# INPUT_STAGE.net
KiCad netlist of a schematic drawn in Altium Designer
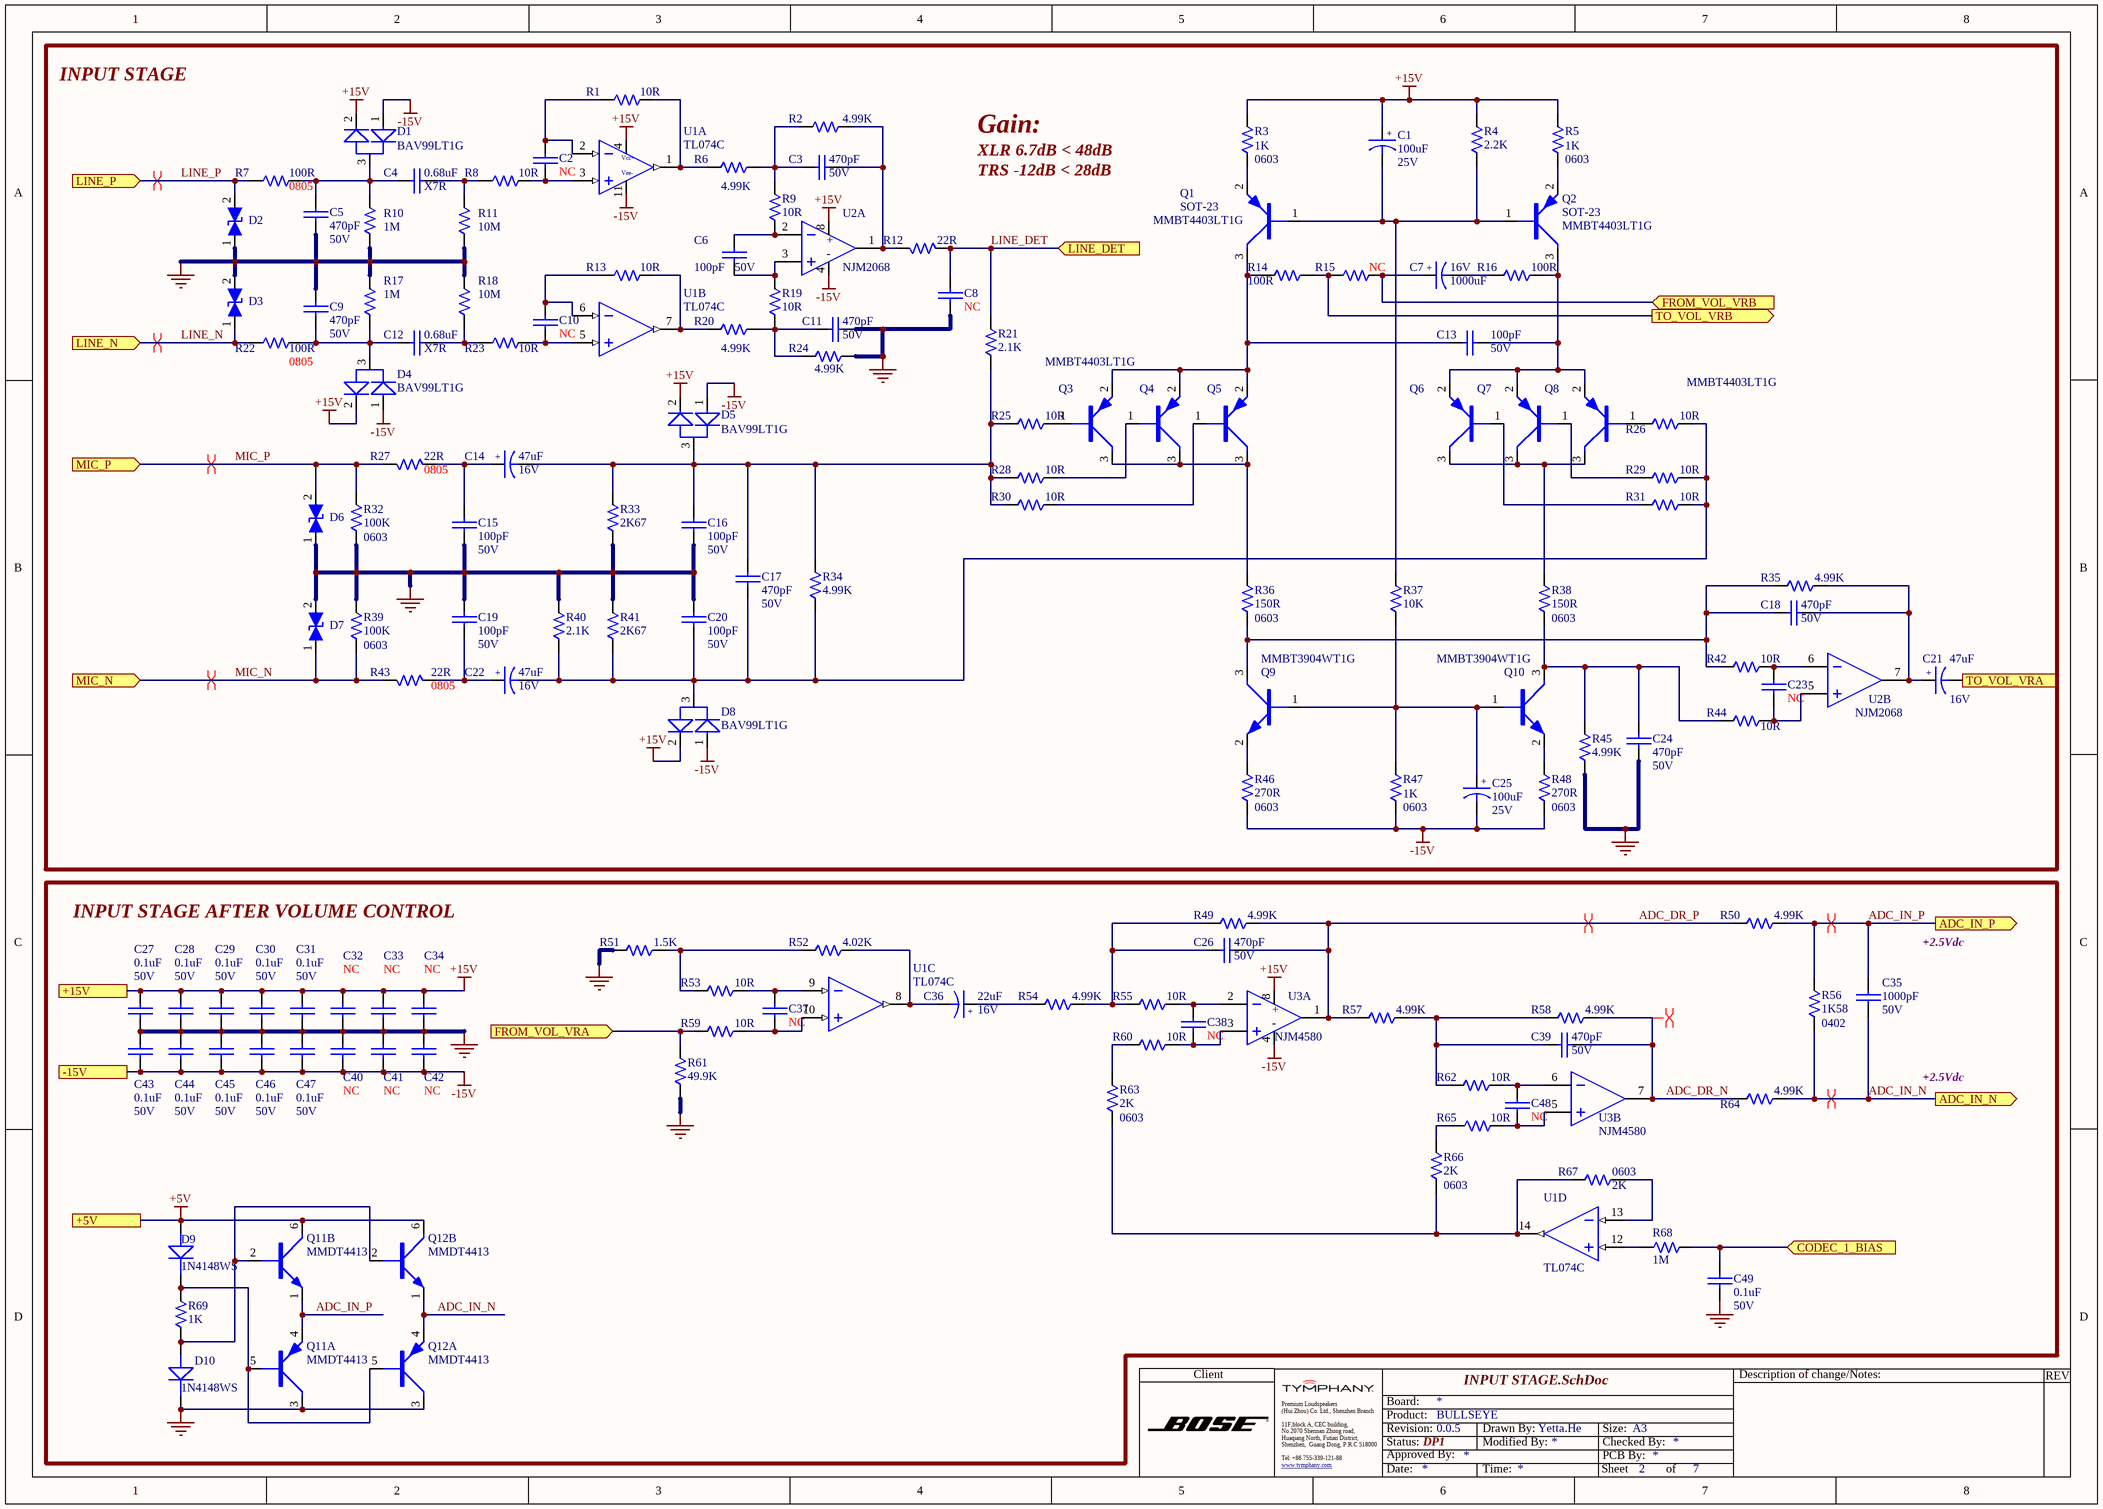
[diagram p0: INPUT STAGE.SchDoc]

(export (version "E")
  (design (tool "Eeschema 10.0.6"))
  (components
    (comp (ref "C1")
      (value "100uF")
      (footprint "CASE - D8")
      (description "E 100UF 25V +-20% 6.3X7. VEJ101M1E K")
      (fields
        (field (name "MFG") "LELON")
        (field (name "MFG PART") "VEJ101M1ETR-0607")
        (field (name "VOLTAGE") "25V")
        (field (name "CREATE_NAME") "Nathan")
      )
      (libsource (lib "P-Capacitors") (part "CAP E 100uF 25V 20% SMD_VEJ101M1ETR-0607"))
    )
    (comp (ref "C2")
      (value "NC")
      (footprint "CAPC0603-RW")
      (fields (field (name "Comment") "CAP0603 NC") (field (name "CREATE_NAME") "Tom"))
      (libsource (lib "Temporary") (part "CAP0603 NC"))
    )
    (comp (ref "C3")
      (value "470pF")
      (footprint "CAPC0603-RW")
      (description "CAP NPO 470PF 50V +-2% 0603 WALSIN L")
      (fields
        (field (name "MFG") "WALSIN")
        (field (name "TOLERANCE") "2%")
        (field (name "VOLTAGE") "50V")
        (field (name "CREATE_NAME") "Nathan")
      )
      (libsource (lib "P-Capacitors") (part "CAP0603 470pF 50V 2%_NPO_WALSIN"))
    )
    (comp (ref "C4")
      (value "0.68uF")
      (footprint "CAPC1206-RW")
      (description "CHIP CAP 0.68uF 25V 10% 1206 X7R")
      (fields
        (field (name "OTHER") "X7R")
        (field (name "TOLERANCE") "10%")
        (field (name "Comment") "PZL456450-6840")
      )
      (libsource (lib "P-Capacitors") (part "CAP1206 0.68uF 25V 10%"))
    )
    (comp (ref "C5")
      (value "470pF")
      (footprint "CAPC0603-RW")
      (description "CAP NPO 470PF 50V +-2% 0603 WALSIN L")
      (fields
        (field (name "MFG") "WALSIN")
        (field (name "TOLERANCE") "2%")
        (field (name "VOLTAGE") "50V")
        (field (name "CREATE_NAME") "Nathan")
      )
      (libsource (lib "P-Capacitors") (part "CAP0603 470pF 50V 2%_NPO_WALSIN"))
    )
    (comp (ref "C6")
      (value "100pF")
      (footprint "CAPC0603-RW")
      (description "CAP NPO 100PF 50V +-2% 0603 WALSIN L")
      (fields
        (field (name "MFG") "WALSIN")
        (field (name "TOLERANCE") "2%")
        (field (name "VOLTAGE") "50V")
        (field (name "CREATE_NAME") "Nathan")
      )
      (libsource (lib "P-Capacitors") (part "CAP0603 100pF 50V 2%_NPO_WALSIN"))
    )
    (comp (ref "C7")
      (value "1000uF")
      (footprint "CAP_Radial_D8L16P3.5")
      (description "E 1000U 16V +-20% 8X15MM RXW102M1C K")
      (fields
        (field (name "MFG") "LELON")
        (field (name "MFG PART") "RXW102M1CBKF0815")
        (field (name "VOLTAGE") "16V")
        (field (name "CREATE_NAME") "Nathan")
      )
      (libsource (lib "P-Capacitors") (part "CAP E Aluminum 1000uF 16V 20%_RXW102M1CBKF0815"))
    )
    (comp (ref "C8")
      (value "NC")
      (footprint "CAPC0603-RW")
      (fields (field (name "Comment") "CAP0603 NC") (field (name "CREATE_NAME") "Tom"))
      (libsource (lib "Temporary") (part "CAP0603 NC"))
    )
    (comp (ref "C9")
      (value "470pF")
      (footprint "CAPC0603-RW")
      (description "CAP NPO 470PF 50V +-2% 0603 WALSIN L")
      (fields
        (field (name "MFG") "WALSIN")
        (field (name "TOLERANCE") "2%")
        (field (name "VOLTAGE") "50V")
        (field (name "CREATE_NAME") "Nathan")
      )
      (libsource (lib "P-Capacitors") (part "CAP0603 470pF 50V 2%_NPO_WALSIN"))
    )
    (comp (ref "C10")
      (value "NC")
      (footprint "CAPC0603-RW")
      (fields (field (name "Comment") "CAP0603 NC") (field (name "CREATE_NAME") "Tom"))
      (libsource (lib "Temporary") (part "CAP0603 NC"))
    )
    (comp (ref "C11")
      (value "470pF")
      (footprint "CAPC0603-RW")
      (description "CAP NPO 470PF 50V +-2% 0603 WALSIN L")
      (fields
        (field (name "MFG") "WALSIN")
        (field (name "TOLERANCE") "2%")
        (field (name "VOLTAGE") "50V")
        (field (name "CREATE_NAME") "Nathan")
      )
      (libsource (lib "P-Capacitors") (part "CAP0603 470pF 50V 2%_NPO_WALSIN"))
    )
    (comp (ref "C12")
      (value "0.68uF")
      (footprint "CAPC1206-RW")
      (description "CHIP CAP 0.68uF 25V 10% 1206 X7R")
      (fields
        (field (name "OTHER") "X7R")
        (field (name "TOLERANCE") "10%")
        (field (name "Comment") "PZL456450-6840")
      )
      (libsource (lib "P-Capacitors") (part "CAP1206 0.68uF 25V 10%"))
    )
    (comp (ref "C13")
      (value "100pF")
      (footprint "CAPC0603-RW")
      (description "CAP NPO 100PF 50V +-2% 0603 WALSIN L")
      (fields
        (field (name "MFG") "WALSIN")
        (field (name "TOLERANCE") "2%")
        (field (name "VOLTAGE") "50V")
        (field (name "CREATE_NAME") "Nathan")
      )
      (libsource (lib "P-Capacitors") (part "CAP0603 100pF 50V 2%_NPO_WALSIN"))
    )
    (comp (ref "C14")
      (value "47uF")
      (footprint "CASE - C5.7")
      (description "E 47UF 16V +-20% 5X6 VEJ470M1C K")
      (fields
        (field (name "MFG") "LELON")
        (field (name "MFG PART") "VEJ470M1CTR-0506")
        (field (name "VOLTAGE") "16V")
        (field (name "CREATE_NAME") "Nathan")
      )
      (libsource (lib "P-Capacitors") (part "CAP E 47uF 16V 20% SMD_VEJ470M1CTR-0506"))
    )
    (comp (ref "C15")
      (value "100pF")
      (footprint "CAPC0603-RW")
      (description "CAP NPO 100PF 50V +-2% 0603 WALSIN L")
      (fields
        (field (name "MFG") "WALSIN")
        (field (name "TOLERANCE") "2%")
        (field (name "VOLTAGE") "50V")
        (field (name "CREATE_NAME") "Nathan")
      )
      (libsource (lib "P-Capacitors") (part "CAP0603 100pF 50V 2%_NPO_WALSIN"))
    )
    (comp (ref "C16")
      (value "100pF")
      (footprint "CAPC0603-RW")
      (description "CAP NPO 100PF 50V +-2% 0603 WALSIN L")
      (fields
        (field (name "MFG") "WALSIN")
        (field (name "TOLERANCE") "2%")
        (field (name "VOLTAGE") "50V")
        (field (name "CREATE_NAME") "Nathan")
      )
      (libsource (lib "P-Capacitors") (part "CAP0603 100pF 50V 2%_NPO_WALSIN"))
    )
    (comp (ref "C17")
      (value "470pF")
      (footprint "CAPC0603-RW")
      (description "CAP NPO 470PF 50V +-2% 0603 WALSIN L")
      (fields
        (field (name "MFG") "WALSIN")
        (field (name "TOLERANCE") "2%")
        (field (name "VOLTAGE") "50V")
        (field (name "CREATE_NAME") "Nathan")
      )
      (libsource (lib "P-Capacitors") (part "CAP0603 470pF 50V 2%_NPO_WALSIN"))
    )
    (comp (ref "C18")
      (value "470pF")
      (footprint "CAPC0603-RW")
      (description "CAP NPO 470PF 50V +-2% 0603 WALSIN L")
      (fields
        (field (name "MFG") "WALSIN")
        (field (name "TOLERANCE") "2%")
        (field (name "VOLTAGE") "50V")
        (field (name "CREATE_NAME") "Nathan")
      )
      (libsource (lib "P-Capacitors") (part "CAP0603 470pF 50V 2%_NPO_WALSIN"))
    )
    (comp (ref "C19")
      (value "100pF")
      (footprint "CAPC0603-RW")
      (description "CAP NPO 100PF 50V +-2% 0603 WALSIN L")
      (fields
        (field (name "MFG") "WALSIN")
        (field (name "TOLERANCE") "2%")
        (field (name "VOLTAGE") "50V")
        (field (name "CREATE_NAME") "Nathan")
      )
      (libsource (lib "P-Capacitors") (part "CAP0603 100pF 50V 2%_NPO_WALSIN"))
    )
    (comp (ref "C20")
      (value "100pF")
      (footprint "CAPC0603-RW")
      (description "CAP NPO 100PF 50V +-2% 0603 WALSIN L")
      (fields
        (field (name "MFG") "WALSIN")
        (field (name "TOLERANCE") "2%")
        (field (name "VOLTAGE") "50V")
        (field (name "CREATE_NAME") "Nathan")
      )
      (libsource (lib "P-Capacitors") (part "CAP0603 100pF 50V 2%_NPO_WALSIN"))
    )
    (comp (ref "C21")
      (value "47uF")
      (footprint "CASE - C5.7")
      (description "E 47UF 16V +-20% 5X6 VEJ470M1C K")
      (fields
        (field (name "MFG") "LELON")
        (field (name "MFG PART") "VEJ470M1CTR-0506")
        (field (name "VOLTAGE") "16V")
        (field (name "CREATE_NAME") "Nathan")
      )
      (libsource (lib "P-Capacitors") (part "CAP E 47uF 16V 20% SMD_VEJ470M1CTR-0506"))
    )
    (comp (ref "C22")
      (value "47uF")
      (footprint "CASE - C5.7")
      (description "E 47UF 16V +-20% 5X6 VEJ470M1C K")
      (fields
        (field (name "MFG") "LELON")
        (field (name "MFG PART") "VEJ470M1CTR-0506")
        (field (name "VOLTAGE") "16V")
        (field (name "CREATE_NAME") "Nathan")
      )
      (libsource (lib "P-Capacitors") (part "CAP E 47uF 16V 20% SMD_VEJ470M1CTR-0506"))
    )
    (comp (ref "C23")
      (value "NC")
      (footprint "CAPC0603-RW")
      (fields (field (name "Comment") "CAP0603 NC") (field (name "CREATE_NAME") "Tom"))
      (libsource (lib "Temporary") (part "CAP0603 NC"))
    )
    (comp (ref "C24")
      (value "470pF")
      (footprint "CAPC0603-RW")
      (description "CAP NPO 470PF 50V +-2% 0603 WALSIN L")
      (fields
        (field (name "MFG") "WALSIN")
        (field (name "TOLERANCE") "2%")
        (field (name "VOLTAGE") "50V")
        (field (name "CREATE_NAME") "Nathan")
      )
      (libsource (lib "P-Capacitors") (part "CAP0603 470pF 50V 2%_NPO_WALSIN"))
    )
    (comp (ref "C25")
      (value "100uF")
      (footprint "CASE - D8")
      (description "E 100UF 25V +-20% 6.3X7. VEJ101M1E K")
      (fields
        (field (name "MFG") "LELON")
        (field (name "MFG PART") "VEJ101M1ETR-0607")
        (field (name "VOLTAGE") "25V")
        (field (name "CREATE_NAME") "Nathan")
      )
      (libsource (lib "P-Capacitors") (part "CAP E 100uF 25V 20% SMD_VEJ101M1ETR-0607"))
    )
    (comp (ref "C26")
      (value "470pF")
      (footprint "CAPC0603-RW")
      (description "CAP NPO 470PF 50V +-2% 0603 WALSIN L")
      (fields
        (field (name "MFG") "WALSIN")
        (field (name "TOLERANCE") "2%")
        (field (name "VOLTAGE") "50V")
        (field (name "CREATE_NAME") "Nathan")
      )
      (libsource (lib "P-Capacitors") (part "CAP0603 470pF 50V 2%_NPO_WALSIN"))
    )
    (comp (ref "C27")
      (value "0.1uF")
      (footprint "CAPC0402-RW")
      (description "CAP, CER, 0.1uF, 10%, 50V, X7R, 0402, RoHS")
      (fields
        (field (name "TOLERANCE") "10%")
        (field (name "VOLTAGE") "50V")
        (field (name "Comment") "PWL456470-1040")
        (field (name "CREATE_NAME") "TOM@Deftronics")
      )
      (libsource (lib "P-Capacitors") (part "CAP0402 0.1uF 50V 10%"))
    )
    (comp (ref "C28")
      (value "0.1uF")
      (footprint "CAPC0402-RW")
      (description "CAP, CER, 0.1uF, 10%, 50V, X7R, 0402, RoHS")
      (fields
        (field (name "TOLERANCE") "10%")
        (field (name "VOLTAGE") "50V")
        (field (name "Comment") "PWL456470-1040")
        (field (name "CREATE_NAME") "TOM@Deftronics")
      )
      (libsource (lib "P-Capacitors") (part "CAP0402 0.1uF 50V 10%"))
    )
    (comp (ref "C29")
      (value "0.1uF")
      (footprint "CAPC0402-RW")
      (description "CAP, CER, 0.1uF, 10%, 50V, X7R, 0402, RoHS")
      (fields
        (field (name "TOLERANCE") "10%")
        (field (name "VOLTAGE") "50V")
        (field (name "Comment") "PWL456470-1040")
        (field (name "CREATE_NAME") "TOM@Deftronics")
      )
      (libsource (lib "P-Capacitors") (part "CAP0402 0.1uF 50V 10%"))
    )
    (comp (ref "C30")
      (value "0.1uF")
      (footprint "CAPC0402-RW")
      (description "CAP, CER, 0.1uF, 10%, 50V, X7R, 0402, RoHS")
      (fields
        (field (name "TOLERANCE") "10%")
        (field (name "VOLTAGE") "50V")
        (field (name "Comment") "PWL456470-1040")
        (field (name "CREATE_NAME") "TOM@Deftronics")
      )
      (libsource (lib "P-Capacitors") (part "CAP0402 0.1uF 50V 10%"))
    )
    (comp (ref "C31")
      (value "0.1uF")
      (footprint "CAPC0402-RW")
      (description "CAP, CER, 0.1uF, 10%, 50V, X7R, 0402, RoHS")
      (fields
        (field (name "TOLERANCE") "10%")
        (field (name "VOLTAGE") "50V")
        (field (name "Comment") "PWL456470-1040")
        (field (name "CREATE_NAME") "TOM@Deftronics")
      )
      (libsource (lib "P-Capacitors") (part "CAP0402 0.1uF 50V 10%"))
    )
    (comp (ref "C32")
      (value "NC")
      (footprint "CAPC0603-RW")
      (fields (field (name "Comment") "CAP0603 NC") (field (name "CREATE_NAME") "Tom"))
      (libsource (lib "Temporary") (part "CAP0603 NC"))
    )
    (comp (ref "C33")
      (value "NC")
      (footprint "CAPC0603-RW")
      (fields (field (name "Comment") "CAP0603 NC") (field (name "CREATE_NAME") "Tom"))
      (libsource (lib "Temporary") (part "CAP0603 NC"))
    )
    (comp (ref "C34")
      (value "NC")
      (footprint "CAPC0603-RW")
      (fields (field (name "Comment") "CAP0603 NC") (field (name "CREATE_NAME") "Tom"))
      (libsource (lib "Temporary") (part "CAP0603 NC"))
    )
    (comp (ref "C35")
      (value "1000pF")
      (footprint "CAPC0603-RW")
      (description "CAP NPO 1000P 50V +-2% 0603 WALSIN L")
      (fields
        (field (name "MFG") "WALSIN")
        (field (name "TOLERANCE") "2%")
        (field (name "VOLTAGE") "50V")
        (field (name "CREATE_NAME") "Nathan")
      )
      (libsource (lib "P-Capacitors") (part "CAP0603 1000pF 50V 2%_NPO_WALSIN"))
    )
    (comp (ref "C36")
      (value "22uF")
      (footprint "CASE - B")
      (description "E 22UF 16V +-20% 4.3X4. VEJ220M1C K")
      (fields
        (field (name "MFG") "LELON")
        (field (name "MFG PART") "VEJ220M1CTR-0405")
        (field (name "VOLTAGE") "16V")
        (field (name "CREATE_NAME") "Nathan")
      )
      (libsource (lib "P-Capacitors") (part "CAP E 22uF 16V 20% SMD_VEJ220M1CTR-0405"))
    )
    (comp (ref "C37")
      (value "NC")
      (footprint "CAPC0603-RW")
      (fields (field (name "Comment") "CAP0603 NC") (field (name "CREATE_NAME") "Tom"))
      (libsource (lib "Temporary") (part "CAP0603 NC"))
    )
    (comp (ref "C38")
      (value "NC")
      (footprint "CAPC0603-RW")
      (fields (field (name "Comment") "CAP0603 NC") (field (name "CREATE_NAME") "Tom"))
      (libsource (lib "Temporary") (part "CAP0603 NC"))
    )
    (comp (ref "C39")
      (value "470pF")
      (footprint "CAPC0603-RW")
      (description "CAP NPO 470PF 50V +-2% 0603 WALSIN L")
      (fields
        (field (name "MFG") "WALSIN")
        (field (name "TOLERANCE") "2%")
        (field (name "VOLTAGE") "50V")
        (field (name "CREATE_NAME") "Nathan")
      )
      (libsource (lib "P-Capacitors") (part "CAP0603 470pF 50V 2%_NPO_WALSIN"))
    )
    (comp (ref "C40")
      (value "NC")
      (footprint "CAPC0603-RW")
      (fields (field (name "Comment") "CAP0603 NC") (field (name "CREATE_NAME") "Tom"))
      (libsource (lib "Temporary") (part "CAP0603 NC"))
    )
    (comp (ref "C41")
      (value "NC")
      (footprint "CAPC0603-RW")
      (fields (field (name "Comment") "CAP0603 NC") (field (name "CREATE_NAME") "Tom"))
      (libsource (lib "Temporary") (part "CAP0603 NC"))
    )
    (comp (ref "C42")
      (value "NC")
      (footprint "CAPC0603-RW")
      (fields (field (name "Comment") "CAP0603 NC") (field (name "CREATE_NAME") "Tom"))
      (libsource (lib "Temporary") (part "CAP0603 NC"))
    )
    (comp (ref "C43")
      (value "0.1uF")
      (footprint "CAPC0402-RW")
      (description "CAP, CER, 0.1uF, 10%, 50V, X7R, 0402, RoHS")
      (fields
        (field (name "TOLERANCE") "10%")
        (field (name "VOLTAGE") "50V")
        (field (name "Comment") "PWL456470-1040")
        (field (name "CREATE_NAME") "TOM@Deftronics")
      )
      (libsource (lib "P-Capacitors") (part "CAP0402 0.1uF 50V 10%"))
    )
    (comp (ref "C44")
      (value "0.1uF")
      (footprint "CAPC0402-RW")
      (description "CAP, CER, 0.1uF, 10%, 50V, X7R, 0402, RoHS")
      (fields
        (field (name "TOLERANCE") "10%")
        (field (name "VOLTAGE") "50V")
        (field (name "Comment") "PWL456470-1040")
        (field (name "CREATE_NAME") "TOM@Deftronics")
      )
      (libsource (lib "P-Capacitors") (part "CAP0402 0.1uF 50V 10%"))
    )
    (comp (ref "C45")
      (value "0.1uF")
      (footprint "CAPC0402-RW")
      (description "CAP, CER, 0.1uF, 10%, 50V, X7R, 0402, RoHS")
      (fields
        (field (name "TOLERANCE") "10%")
        (field (name "VOLTAGE") "50V")
        (field (name "Comment") "PWL456470-1040")
        (field (name "CREATE_NAME") "TOM@Deftronics")
      )
      (libsource (lib "P-Capacitors") (part "CAP0402 0.1uF 50V 10%"))
    )
    (comp (ref "C46")
      (value "0.1uF")
      (footprint "CAPC0402-RW")
      (description "CAP, CER, 0.1uF, 10%, 50V, X7R, 0402, RoHS")
      (fields
        (field (name "TOLERANCE") "10%")
        (field (name "VOLTAGE") "50V")
        (field (name "Comment") "PWL456470-1040")
        (field (name "CREATE_NAME") "TOM@Deftronics")
      )
      (libsource (lib "P-Capacitors") (part "CAP0402 0.1uF 50V 10%"))
    )
    (comp (ref "C47")
      (value "0.1uF")
      (footprint "CAPC0402-RW")
      (description "CAP, CER, 0.1uF, 10%, 50V, X7R, 0402, RoHS")
      (fields
        (field (name "TOLERANCE") "10%")
        (field (name "VOLTAGE") "50V")
        (field (name "Comment") "PWL456470-1040")
        (field (name "CREATE_NAME") "TOM@Deftronics")
      )
      (libsource (lib "P-Capacitors") (part "CAP0402 0.1uF 50V 10%"))
    )
    (comp (ref "C48")
      (value "NC")
      (footprint "CAPC0603-RW")
      (fields (field (name "Comment") "CAP0603 NC") (field (name "CREATE_NAME") "Tom"))
      (libsource (lib "Temporary") (part "CAP0603 NC"))
    )
    (comp (ref "C49")
      (value "0.1uF")
      (footprint "CAPC0402-RW")
      (description "CAP, CER, 0.1uF, 10%, 50V, X7R, 0402, RoHS")
      (fields
        (field (name "TOLERANCE") "10%")
        (field (name "VOLTAGE") "50V")
        (field (name "Comment") "PWL456470-1040")
        (field (name "CREATE_NAME") "TOM@Deftronics")
      )
      (libsource (lib "P-Capacitors") (part "CAP0402 0.1uF 50V 10%"))
    )
    (comp (ref "D1")
      (value "RCD100099-0010")
      (footprint "SOT23-132-RW")
      (description "SWITC 70V 215MA BAV99LT1G ON SE G")
      (fields
        (field (name "MFG") "ON SEMI")
        (field (name "VOLTAGE") "100V")
        (field (name "MFG PART") "BAV99LT1G")
      )
      (libsource (lib "R-Semiconductors") (part "BAV99LT1G"))
    )
    (comp (ref "D2")
      (value "T710500020400")
      (footprint "VAR-0402")
      (description "VR AVRM1005C120MTAAB TDK K")
      (fields
        (field (name "MFG") "TDK")
        (field (name "MFG PART") "AVRM1005C120MTAAB")
        (field (name "CREAT NAME") "QCD")
      )
      (libsource (lib "R-Semiconductors") (part "AVRM1005C120MTAAB"))
    )
    (comp (ref "D3")
      (value "T710500020400")
      (footprint "VAR-0402")
      (description "VR AVRM1005C120MTAAB TDK K")
      (fields
        (field (name "MFG") "TDK")
        (field (name "MFG PART") "AVRM1005C120MTAAB")
        (field (name "CREAT NAME") "QCD")
      )
      (libsource (lib "R-Semiconductors") (part "AVRM1005C120MTAAB"))
    )
    (comp (ref "D4")
      (value "RCD100099-0010")
      (footprint "SOT23-132-RW")
      (description "SWITC 70V 215MA BAV99LT1G ON SE G")
      (fields
        (field (name "MFG") "ON SEMI")
        (field (name "VOLTAGE") "100V")
        (field (name "MFG PART") "BAV99LT1G")
      )
      (libsource (lib "R-Semiconductors") (part "BAV99LT1G"))
    )
    (comp (ref "D5")
      (value "RCD100099-0010")
      (footprint "SOT23-132-RW")
      (description "SWITC 70V 215MA BAV99LT1G ON SE G")
      (fields
        (field (name "MFG") "ON SEMI")
        (field (name "VOLTAGE") "100V")
        (field (name "MFG PART") "BAV99LT1G")
      )
      (libsource (lib "R-Semiconductors") (part "BAV99LT1G"))
    )
    (comp (ref "D6")
      (value "T710500020400")
      (footprint "VAR-0402")
      (description "VR AVRM1005C120MTAAB TDK K")
      (fields
        (field (name "MFG") "TDK")
        (field (name "MFG PART") "AVRM1005C120MTAAB")
        (field (name "CREAT NAME") "QCD")
      )
      (libsource (lib "R-Semiconductors") (part "AVRM1005C120MTAAB"))
    )
    (comp (ref "D7")
      (value "T710500020400")
      (footprint "VAR-0402")
      (description "VR AVRM1005C120MTAAB TDK K")
      (fields
        (field (name "MFG") "TDK")
        (field (name "MFG PART") "AVRM1005C120MTAAB")
        (field (name "CREAT NAME") "QCD")
      )
      (libsource (lib "R-Semiconductors") (part "AVRM1005C120MTAAB"))
    )
    (comp (ref "D8")
      (value "RCD100099-0010")
      (footprint "SOT23-132-RW")
      (description "SWITC 70V 215MA BAV99LT1G ON SE G")
      (fields
        (field (name "MFG") "ON SEMI")
        (field (name "VOLTAGE") "100V")
        (field (name "MFG PART") "BAV99LT1G")
      )
      (libsource (lib "R-Semiconductors") (part "BAV99LT1G"))
    )
    (comp (ref "D9")
      (value "RCD114148-0020")
      (footprint "SOD-323")
      (description "DIODE SW 1N4148 VF=0.7V SOD-323")
      (fields
        (field (name "MFG") "TW SEMICONDUCTOR")
        (field (name "VOLTAGE") "100V")
        (field (name "MFG PART") "1N4148WS")
      )
      (libsource (lib "R-Semiconductors") (part "1N4148WS"))
    )
    (comp (ref "D10")
      (value "RCD114148-0020")
      (footprint "SOD-323")
      (description "DIODE SW 1N4148 VF=0.7V SOD-323")
      (fields
        (field (name "MFG") "TW SEMICONDUCTOR")
        (field (name "VOLTAGE") "100V")
        (field (name "MFG PART") "1N4148WS")
      )
      (libsource (lib "R-Semiconductors") (part "1N4148WS"))
    )
    (comp (ref "Q1")
      (value "T582003100440")
      (footprint "SOT23-132-RW")
      (description "PNP -40V MMBT4403LT1G SOT23 ON K")
      (fields
        (field (name "MFG") "ON")
        (field (name "VOLTAGE") "40V")
        (field (name "PACKAGE") "SOT-23")
        (field (name "MFG PART") "MMBT4403LT1G")
        (field (name "CREATE NAME") "Nathan")
      )
      (libsource (lib "R-Semiconductors") (part "MMBT4403LT1G"))
    )
    (comp (ref "Q2")
      (value "T582003100440")
      (footprint "SOT23-132-RW")
      (description "PNP -40V MMBT4403LT1G SOT23 ON K")
      (fields
        (field (name "MFG") "ON")
        (field (name "VOLTAGE") "40V")
        (field (name "PACKAGE") "SOT-23")
        (field (name "MFG PART") "MMBT4403LT1G")
        (field (name "CREATE NAME") "Nathan")
      )
      (libsource (lib "R-Semiconductors") (part "MMBT4403LT1G"))
    )
    (comp (ref "Q3")
      (value "T582003100440")
      (footprint "SOT23-132-RW")
      (description "PNP -40V MMBT4403LT1G SOT23 ON K")
      (fields
        (field (name "MFG") "ON")
        (field (name "VOLTAGE") "40V")
        (field (name "MFG PART") "MMBT4403LT1G")
        (field (name "CREATE NAME") "Nathan")
      )
      (libsource (lib "R-Semiconductors") (part "MMBT4403LT1G"))
    )
    (comp (ref "Q4")
      (value "T582003100440")
      (footprint "SOT23-132-RW")
      (description "PNP -40V MMBT4403LT1G SOT23 ON K")
      (fields (field (name "MFG") "ON") (field (name "VOLTAGE") "40V") (field (name "CREATE NAME") "Nathan"))
      (libsource (lib "R-Semiconductors") (part "MMBT4403LT1G"))
    )
    (comp (ref "Q5")
      (value "T582003100440")
      (footprint "SOT23-132-RW")
      (description "PNP -40V MMBT4403LT1G SOT23 ON K")
      (fields (field (name "MFG") "ON") (field (name "VOLTAGE") "40V") (field (name "CREATE NAME") "Nathan"))
      (libsource (lib "R-Semiconductors") (part "MMBT4403LT1G"))
    )
    (comp (ref "Q6")
      (value "T582003100440")
      (footprint "SOT23-132-RW")
      (description "PNP -40V MMBT4403LT1G SOT23 ON K")
      (fields (field (name "MFG") "ON") (field (name "VOLTAGE") "40V") (field (name "CREATE NAME") "Nathan"))
      (libsource (lib "R-Semiconductors") (part "MMBT4403LT1G"))
    )
    (comp (ref "Q7")
      (value "T582003100440")
      (footprint "SOT23-132-RW")
      (description "PNP -40V MMBT4403LT1G SOT23 ON K")
      (fields (field (name "MFG") "ON") (field (name "VOLTAGE") "40V") (field (name "CREATE NAME") "Nathan"))
      (libsource (lib "R-Semiconductors") (part "MMBT4403LT1G"))
    )
    (comp (ref "Q8")
      (value "T582003100440")
      (footprint "SOT23-132-RW")
      (description "PNP -40V MMBT4403LT1G SOT23 ON K")
      (fields
        (field (name "MFG") "ON")
        (field (name "VOLTAGE") "40V")
        (field (name "MFG PART") "MMBT4403LT1G")
        (field (name "CREATE NAME") "Nathan")
      )
      (libsource (lib "R-Semiconductors") (part "MMBT4403LT1G"))
    )
    (comp (ref "Q9")
      (value "T581004222440")
      (footprint "SOT323(SC-70)-R")
      (description "NPN 40V MMBT3904WT1G SC70 ( ON K")
      (fields
        (field (name "MFG") "ON")
        (field (name "MFG PART") "MMBT3904WT1G")
        (field (name "CREATE_NAME") "Nathan")
      )
      (libsource (lib "R-Semiconductors") (part "MMBT3904WT1G"))
    )
    (comp (ref "Q10")
      (value "T581004222440")
      (footprint "SOT323(SC-70)-R")
      (description "NPN 40V MMBT3904WT1G SC70 ( ON K")
      (fields
        (field (name "MFG") "ON")
        (field (name "MFG PART") "MMBT3904WT1G")
        (field (name "CREATE_NAME") "Nathan")
      )
      (libsource (lib "R-Semiconductors") (part "MMBT3904WT1G"))
    )
    (comp (ref "Q11")
      (value "RCC004413-0010")
      (footprint "SOT-363")
      (description "COMPOSOTE TRANSISTOR SOT-363 MMDT4413")
      (fields
        (field (name "MFG") "DIODES")
        (field (name "MFG_PART") "MMDT4413")
        (field (name "CREATE_NAME") "Nathan")
      )
      (libsource (lib "R-Semiconductors") (part "MMDT4413"))
    )
    (comp (ref "Q12")
      (value "RCC004413-0010")
      (footprint "SOT-363")
      (description "COMPOSOTE TRANSISTOR SOT-363 MMDT4413")
      (fields
        (field (name "MFG") "DIODES")
        (field (name "MFG_PART") "MMDT4413")
        (field (name "CREATE_NAME") "Nathan")
      )
      (libsource (lib "R-Semiconductors") (part "MMDT4413"))
    )
    (comp (ref "R1")
      (value "10R")
      (footprint "0603-RW")
      (description "CHIP 10 OHM 100PPM +-1% 0603 WALS L")
      (fields (field (name "POWER") "1/10W") (field (name "MFG") "WALSIN (華新)"))
      (libsource (lib "Q-Resistors") (part "RES0603 1/10W 1% 10 OHM"))
    )
    (comp (ref "R2")
      (value "4.99K")
      (footprint "0603-RW")
      (description "GP CHIP RES. 4.99K OHM 1/10W 1% 0603")
      (fields (field (name "POWER") "1/10W") (field (name "Comment") "QCF011030-4991"))
      (libsource (lib "Q-Resistors") (part "RES0603 1/10W 1% 4.99K OHM"))
    )
    (comp (ref "R3")
      (value "1K")
      (footprint "0603-RW")
      (description "GP CHIP RES. 1K OHM 1/10W 1% 0603")
      (fields
        (field (name "POWER") "1/10W")
        (field (name "PACKAGE") "0603")
        (field (name "Comment") "QCF011030-1001")
      )
      (libsource (lib "Q-Resistors") (part "RES0603 1/10W 1% 1K OHM"))
    )
    (comp (ref "R4")
      (value "2.2K")
      (footprint "0603-RW")
      (description "GP CHIP RES. 2.2K OHM 1/10W 1% 0603")
      (fields (field (name "POWER") "1/10W") (field (name "Comment") "QCF011030-2201"))
      (libsource (lib "Q-Resistors") (part "RES0603 1/10W 1% 2.2K OHM"))
    )
    (comp (ref "R5")
      (value "1K")
      (footprint "0603-RW")
      (description "GP CHIP RES. 1K OHM 1/10W 1% 0603")
      (fields
        (field (name "POWER") "1/10W")
        (field (name "PACKAGE") "0603")
        (field (name "Comment") "QCF011030-1001")
      )
      (libsource (lib "Q-Resistors") (part "RES0603 1/10W 1% 1K OHM"))
    )
    (comp (ref "R6")
      (value "4.99K")
      (footprint "0603-RW")
      (description "GP CHIP RES. 4.99K OHM 1/10W 1% 0603")
      (fields (field (name "POWER") "1/10W") (field (name "Comment") "QCF011030-4991"))
      (libsource (lib "Q-Resistors") (part "RES0603 1/10W 1% 4.99K OHM"))
    )
    (comp (ref "R7")
      (value "100R")
      (footprint "0805-RW")
      (description "GP CHIP RES. 100 OHM 1/8W 1% 0805")
      (fields
        (field (name "POWER") "1/8W")
        (field (name "MFG") "WALSIN (華新)")
        (field (name "PACKAGE") "0805")
      )
      (libsource (lib "Q-Resistors") (part "RES0805 1/8W 1% 100 OHM"))
    )
    (comp (ref "R8")
      (value "10R")
      (footprint "0603-RW")
      (description "CHIP 10 OHM 100PPM +-1% 0603 WALS L")
      (fields (field (name "POWER") "1/10W") (field (name "MFG") "WALSIN (華新)"))
      (libsource (lib "Q-Resistors") (part "RES0603 1/10W 1% 10 OHM"))
    )
    (comp (ref "R9")
      (value "10R")
      (footprint "0603-RW")
      (description "CHIP 10 OHM 100PPM +-1% 0603 WALS L")
      (fields (field (name "POWER") "1/10W") (field (name "MFG") "WALSIN (華新)"))
      (libsource (lib "Q-Resistors") (part "RES0603 1/10W 1% 10 OHM"))
    )
    (comp (ref "R10")
      (value "1M")
      (footprint "0603-RW")
      (description "GP CHIP RES. 1M OHM 1/10W 1% 0603")
      (fields (field (name "Comment") "QCF011030-1004"))
      (libsource (lib "Q-Resistors") (part "RES0603 1/10W 1% 1M OHM"))
    )
    (comp (ref "R11")
      (value "10M")
      (footprint "0603-RW")
      (description "CHIP RES. 10M OHM 1/10W 1% 0603")
      (fields (field (name "Comment") "QCF011030-1005"))
      (libsource (lib "Q-Resistors") (part "RES0603 1/10W 1% 10M OHM"))
    )
    (comp (ref "R12")
      (value "22R")
      (footprint "0805-RW")
      (description "CHIP RES 22 OHM 1/8W 1% 0805")
      (fields (field (name "POWER") "1/8W") (field (name "Comment") "QCF081020-2209"))
      (libsource (lib "Q-Resistors") (part "RES0805 1/8W 1% 22 OHM"))
    )
    (comp (ref "R13")
      (value "10R")
      (footprint "0603-RW")
      (description "CHIP 10 OHM 100PPM +-1% 0603 WALS L")
      (fields (field (name "POWER") "1/10W") (field (name "MFG") "WALSIN (華新)"))
      (libsource (lib "Q-Resistors") (part "RES0603 1/10W 1% 10 OHM"))
    )
    (comp (ref "R14")
      (value "100R")
      (footprint "0402-RW")
      (description "CHIP RES 100 OHM 1/16W 1% 0402")
      (fields (field (name "MFG") "WALSIN") (field (name "Comment") "QCF161240-1000"))
      (libsource (lib "Q-Resistors") (part "RES0402 1/16W 1% 100 OHM"))
    )
    (comp (ref "R15")
      (value "NC")
      (footprint "0603-RW")
      (fields (field (name "Comment") "RES0603 NC") (field (name "CREATE_NAME") "Tom"))
      (libsource (lib "Temporary") (part "RES0603 NC"))
    )
    (comp (ref "R16")
      (value "100R")
      (footprint "0402-RW")
      (description "CHIP RES 100 OHM 1/16W 1% 0402")
      (fields (field (name "MFG") "WALSIN") (field (name "Comment") "QCF161240-1000"))
      (libsource (lib "Q-Resistors") (part "RES0402 1/16W 1% 100 OHM"))
    )
    (comp (ref "R17")
      (value "1M")
      (footprint "0603-RW")
      (description "GP CHIP RES. 1M OHM 1/10W 1% 0603")
      (fields (field (name "Comment") "QCF011030-1004"))
      (libsource (lib "Q-Resistors") (part "RES0603 1/10W 1% 1M OHM"))
    )
    (comp (ref "R18")
      (value "10M")
      (footprint "0603-RW")
      (description "CHIP RES. 10M OHM 1/10W 1% 0603")
      (fields (field (name "Comment") "QCF011030-1005"))
      (libsource (lib "Q-Resistors") (part "RES0603 1/10W 1% 10M OHM"))
    )
    (comp (ref "R19")
      (value "10R")
      (footprint "0603-RW")
      (description "CHIP 10 OHM 100PPM +-1% 0603 WALS L")
      (fields (field (name "POWER") "1/10W") (field (name "MFG") "WALSIN (華新)"))
      (libsource (lib "Q-Resistors") (part "RES0603 1/10W 1% 10 OHM"))
    )
    (comp (ref "R20")
      (value "4.99K")
      (footprint "0603-RW")
      (description "GP CHIP RES. 4.99K OHM 1/10W 1% 0603")
      (fields (field (name "POWER") "1/10W") (field (name "Comment") "QCF011030-4991"))
      (libsource (lib "Q-Resistors") (part "RES0603 1/10W 1% 4.99K OHM"))
    )
    (comp (ref "R21")
      (value "2.1K")
      (footprint "0603-RW")
      (description "CHIP RES 2.1K OHM 1/10W  1% 0603")
      (fields (field (name "POWER") "1/10W") (field (name "Comment") "QCF011030-2101"))
      (libsource (lib "Q-Resistors") (part "RES0603 1/10W 1% 2.1K OHM"))
    )
    (comp (ref "R22")
      (value "100R")
      (footprint "0805-RW")
      (description "GP CHIP RES. 100 OHM 1/8W 1% 0805")
      (fields
        (field (name "POWER") "1/8W")
        (field (name "MFG") "WALSIN (華新)")
        (field (name "PACKAGE") "0805")
      )
      (libsource (lib "Q-Resistors") (part "RES0805 1/8W 1% 100 OHM"))
    )
    (comp (ref "R23")
      (value "10R")
      (footprint "0603-RW")
      (description "CHIP 10 OHM 100PPM +-1% 0603 WALS L")
      (fields (field (name "POWER") "1/10W") (field (name "MFG") "WALSIN (華新)"))
      (libsource (lib "Q-Resistors") (part "RES0603 1/10W 1% 10 OHM"))
    )
    (comp (ref "R24")
      (value "4.99K")
      (footprint "0603-RW")
      (description "GP CHIP RES. 4.99K OHM 1/10W 1% 0603")
      (fields (field (name "POWER") "1/10W") (field (name "Comment") "QCF011030-4991"))
      (libsource (lib "Q-Resistors") (part "RES0603 1/10W 1% 4.99K OHM"))
    )
    (comp (ref "R25")
      (value "10R")
      (footprint "0603-RW")
      (description "CHIP 10 OHM 100PPM +-1% 0603 WALS L")
      (fields (field (name "POWER") "1/10W") (field (name "MFG") "WALSIN (華新)"))
      (libsource (lib "Q-Resistors") (part "RES0603 1/10W 1% 10 OHM"))
    )
    (comp (ref "R26")
      (value "10R")
      (footprint "0603-RW")
      (description "CHIP 10 OHM 100PPM +-1% 0603 WALS L")
      (fields (field (name "POWER") "1/10W") (field (name "MFG") "WALSIN (華新)"))
      (libsource (lib "Q-Resistors") (part "RES0603 1/10W 1% 10 OHM"))
    )
    (comp (ref "R27")
      (value "22R")
      (footprint "0805-RW")
      (description "CHIP RES 22 OHM 1/8W 1% 0805")
      (fields
        (field (name "POWER") "1/8W")
        (field (name "PACKAGE") "0805")
        (field (name "Comment") "QCF081020-2209")
      )
      (libsource (lib "Q-Resistors") (part "RES0805 1/8W 1% 22 OHM"))
    )
    (comp (ref "R28")
      (value "10R")
      (footprint "0603-RW")
      (description "CHIP 10 OHM 100PPM +-1% 0603 WALS L")
      (fields (field (name "POWER") "1/10W") (field (name "MFG") "WALSIN (華新)"))
      (libsource (lib "Q-Resistors") (part "RES0603 1/10W 1% 10 OHM"))
    )
    (comp (ref "R29")
      (value "10R")
      (footprint "0603-RW")
      (description "CHIP 10 OHM 100PPM +-1% 0603 WALS L")
      (fields (field (name "POWER") "1/10W") (field (name "MFG") "WALSIN (華新)"))
      (libsource (lib "Q-Resistors") (part "RES0603 1/10W 1% 10 OHM"))
    )
    (comp (ref "R30")
      (value "10R")
      (footprint "0603-RW")
      (description "CHIP 10 OHM 100PPM +-1% 0603 WALS L")
      (fields (field (name "POWER") "1/10W") (field (name "MFG") "WALSIN (華新)"))
      (libsource (lib "Q-Resistors") (part "RES0603 1/10W 1% 10 OHM"))
    )
    (comp (ref "R31")
      (value "10R")
      (footprint "0603-RW")
      (description "CHIP 10 OHM 100PPM +-1% 0603 WALS L")
      (fields (field (name "POWER") "1/10W") (field (name "MFG") "WALSIN (華新)"))
      (libsource (lib "Q-Resistors") (part "RES0603 1/10W 1% 10 OHM"))
    )
    (comp (ref "R32")
      (value "100K")
      (footprint "0603-RW")
      (description "GP CHIP RES. 100K OHM 1/10W 1% 0603")
      (fields
        (field (name "POWER") "1/10W")
        (field (name "PACKAGE") "0603")
        (field (name "Comment") "QCF011030-1003")
      )
      (libsource (lib "Q-Resistors") (part "RES0603 1/10W 1% 100K OHM"))
    )
    (comp (ref "R33")
      (value "2K67")
      (footprint "0603-RW")
      (description "CHIP 2.67K OHM 100PPM +-1% 0603 WALS L")
      (fields
        (field (name "POWER") "1/10W")
        (field (name "MFG") "WALSIN (華新)")
        (field (name "CREATE_NAME") "Nathan")
      )
      (libsource (lib "Q-Resistors") (part "RES0603 1/10W 1% 2.67K OHM_WALSIN"))
    )
    (comp (ref "R34")
      (value "4.99K")
      (footprint "0603-RW")
      (description "GP CHIP RES. 4.99K OHM 1/10W 1% 0603")
      (fields (field (name "POWER") "1/10W") (field (name "Comment") "QCF011030-4991"))
      (libsource (lib "Q-Resistors") (part "RES0603 1/10W 1% 4.99K OHM"))
    )
    (comp (ref "R35")
      (value "4.99K")
      (footprint "0603-RW")
      (description "GP CHIP RES. 4.99K OHM 1/10W 1% 0603")
      (fields (field (name "POWER") "1/10W") (field (name "Comment") "QCF011030-4991"))
      (libsource (lib "Q-Resistors") (part "RES0603 1/10W 1% 4.99K OHM"))
    )
    (comp (ref "R36")
      (value "150R")
      (footprint "0603-RW")
      (description "GP CHIP RES. 150 OHM 1/10W 1% 0603")
      (fields
        (field (name "POWER") "1/10W")
        (field (name "PACKAGE") "0603")
        (field (name "Comment") "QCF011030-1500")
      )
      (libsource (lib "Q-Resistors") (part "RES0603 1/10W 1% 150 OHM"))
    )
    (comp (ref "R37")
      (value "10K")
      (footprint "0603-RW")
      (description "GP CHIP RES. 10K OHM 1/10W 1% 0603")
      (fields (field (name "Comment") "QCF011030-1002"))
      (libsource (lib "Q-Resistors") (part "RES0603 1/10W 1% 10K OHM"))
    )
    (comp (ref "R38")
      (value "150R")
      (footprint "0603-RW")
      (description "GP CHIP RES. 150 OHM 1/10W 1% 0603")
      (fields
        (field (name "POWER") "1/10W")
        (field (name "PACKAGE") "0603")
        (field (name "Comment") "QCF011030-1500")
      )
      (libsource (lib "Q-Resistors") (part "RES0603 1/10W 1% 150 OHM"))
    )
    (comp (ref "R39")
      (value "100K")
      (footprint "0603-RW")
      (description "GP CHIP RES. 100K OHM 1/10W 1% 0603")
      (fields
        (field (name "POWER") "1/10W")
        (field (name "PACKAGE") "0603")
        (field (name "Comment") "QCF011030-1003")
      )
      (libsource (lib "Q-Resistors") (part "RES0603 1/10W 1% 100K OHM"))
    )
    (comp (ref "R40")
      (value "2.1K")
      (footprint "0603-RW")
      (description "CHIP RES 2.1K OHM 1/10W  1% 0603")
      (fields (field (name "POWER") "1/10W") (field (name "Comment") "QCF011030-2101"))
      (libsource (lib "Q-Resistors") (part "RES0603 1/10W 1% 2.1K OHM"))
    )
    (comp (ref "R41")
      (value "2K67")
      (footprint "0603-RW")
      (description "CHIP 2.67K OHM 100PPM +-1% 0603 WALS L")
      (fields
        (field (name "POWER") "1/10W")
        (field (name "MFG") "WALSIN (華新)")
        (field (name "CREATE_NAME") "Nathan")
      )
      (libsource (lib "Q-Resistors") (part "RES0603 1/10W 1% 2.67K OHM_WALSIN"))
    )
    (comp (ref "R42")
      (value "10R")
      (footprint "0603-RW")
      (description "CHIP 10 OHM 100PPM +-1% 0603 WALS L")
      (fields (field (name "POWER") "1/10W") (field (name "MFG") "WALSIN (華新)"))
      (libsource (lib "Q-Resistors") (part "RES0603 1/10W 1% 10 OHM"))
    )
    (comp (ref "R43")
      (value "22R")
      (footprint "0805-RW")
      (description "CHIP RES 22 OHM 1/8W 1% 0805")
      (fields
        (field (name "POWER") "1/8W")
        (field (name "PACKAGE") "0805")
        (field (name "Comment") "QCF081020-2209")
      )
      (libsource (lib "Q-Resistors") (part "RES0805 1/8W 1% 22 OHM"))
    )
    (comp (ref "R44")
      (value "10R")
      (footprint "0603-RW")
      (description "CHIP 10 OHM 100PPM +-1% 0603 WALS L")
      (fields (field (name "POWER") "1/10W") (field (name "MFG") "WALSIN (華新)"))
      (libsource (lib "Q-Resistors") (part "RES0603 1/10W 1% 10 OHM"))
    )
    (comp (ref "R45")
      (value "4.99K")
      (footprint "0603-RW")
      (description "GP CHIP RES. 4.99K OHM 1/10W 1% 0603")
      (fields (field (name "POWER") "1/10W") (field (name "Comment") "QCF011030-4991"))
      (libsource (lib "Q-Resistors") (part "RES0603 1/10W 1% 4.99K OHM"))
    )
    (comp (ref "R46")
      (value "270R")
      (footprint "0603-RW")
      (description "CHIP RES 270 OHM 1/10W 1% 0603")
      (fields
        (field (name "POWER") "1/10W")
        (field (name "PACKAGE") "0603")
        (field (name "Comment") "QCF011030-2700")
      )
      (libsource (lib "Q-Resistors") (part "RES0603 1/10W 1% 270 OHM"))
    )
    (comp (ref "R47")
      (value "1K")
      (footprint "0603-RW")
      (description "GP CHIP RES. 1K OHM 1/10W 1% 0603")
      (fields
        (field (name "POWER") "1/10W")
        (field (name "PACKAGE") "0603")
        (field (name "Comment") "QCF011030-1001")
      )
      (libsource (lib "Q-Resistors") (part "RES0603 1/10W 1% 1K OHM"))
    )
    (comp (ref "R48")
      (value "270R")
      (footprint "0603-RW")
      (description "CHIP RES 270 OHM 1/10W 1% 0603")
      (fields
        (field (name "POWER") "1/10W")
        (field (name "PACKAGE") "0603")
        (field (name "Comment") "QCF011030-2700")
      )
      (libsource (lib "Q-Resistors") (part "RES0603 1/10W 1% 270 OHM"))
    )
    (comp (ref "R49")
      (value "4.99K")
      (footprint "0603-RW")
      (description "GP CHIP RES. 4.99K OHM 1/10W 1% 0603")
      (fields (field (name "POWER") "1/10W") (field (name "Comment") "QCF011030-4991"))
      (libsource (lib "Q-Resistors") (part "RES0603 1/10W 1% 4.99K OHM"))
    )
    (comp (ref "R50")
      (value "4.99K")
      (footprint "0603-RW")
      (description "GP CHIP RES. 4.99K OHM 1/10W 1% 0603")
      (fields (field (name "POWER") "1/10W") (field (name "Comment") "QCF011030-4991"))
      (libsource (lib "Q-Resistors") (part "RES0603 1/10W 1% 4.99K OHM"))
    )
    (comp (ref "R51")
      (value "1.5K")
      (footprint "0603-RW")
      (description "GP CHIP RES. 1.5K OHM 1/10W 1% 0603")
      (fields (field (name "POWER") "1/10W") (field (name "Comment") "QCF011030-1501"))
      (libsource (lib "Q-Resistors") (part "RES0603 1/10W 1% 1.5K OHM"))
    )
    (comp (ref "R52")
      (value "4.02K")
      (footprint "0603-RW")
      (description "CHIP 4.02K OHM 100PPM +-1% 0603 WALS L")
      (fields
        (field (name "POWER") "1/10W")
        (field (name "Comment") "T502402102399")
        (field (name "CREATE_NAME") "Tom")
      )
      (libsource (lib "Q-Resistors") (part "RES0603 1/10W 1% 4.02KOHM"))
    )
    (comp (ref "R53")
      (value "10R")
      (footprint "0603-RW")
      (description "CHIP 10 OHM 100PPM +-1% 0603 WALS L")
      (fields (field (name "POWER") "1/10W") (field (name "MFG") "WALSIN (華新)"))
      (libsource (lib "Q-Resistors") (part "RES0603 1/10W 1% 10 OHM"))
    )
    (comp (ref "R54")
      (value "4.99K")
      (footprint "0603-RW")
      (description "GP CHIP RES. 4.99K OHM 1/10W 1% 0603")
      (fields (field (name "POWER") "1/10W") (field (name "Comment") "QCF011030-4991"))
      (libsource (lib "Q-Resistors") (part "RES0603 1/10W 1% 4.99K OHM"))
    )
    (comp (ref "R55")
      (value "10R")
      (footprint "0603-RW")
      (description "CHIP 10 OHM 100PPM +-1% 0603 WALS L")
      (fields (field (name "POWER") "1/10W") (field (name "MFG") "WALSIN (華新)"))
      (libsource (lib "Q-Resistors") (part "RES0603 1/10W 1% 10 OHM"))
    )
    (comp (ref "R56")
      (value "1K58")
      (footprint "0402-RW")
      (description "CHIP 1.58K OHM 100PPM +-1% 0402 WALS L")
      (fields
        (field (name "POWER") "1/16W")
        (field (name "MFG") "WALSIN (華新)")
        (field (name "PACKAGE") "0402")
        (field (name "CREATE_NAME") "Nathan")
      )
      (libsource (lib "Q-Resistors") (part "RES0402 1/16W 1% 1.58K OMH_WALSIN"))
    )
    (comp (ref "R57")
      (value "4.99K")
      (footprint "0603-RW")
      (description "GP CHIP RES. 4.99K OHM 1/10W 1% 0603")
      (fields (field (name "POWER") "1/10W") (field (name "Comment") "QCF011030-4991"))
      (libsource (lib "Q-Resistors") (part "RES0603 1/10W 1% 4.99K OHM"))
    )
    (comp (ref "R58")
      (value "4.99K")
      (footprint "0603-RW")
      (description "GP CHIP RES. 4.99K OHM 1/10W 1% 0603")
      (fields (field (name "POWER") "1/10W") (field (name "Comment") "QCF011030-4991"))
      (libsource (lib "Q-Resistors") (part "RES0603 1/10W 1% 4.99K OHM"))
    )
    (comp (ref "R59")
      (value "10R")
      (footprint "0603-RW")
      (description "CHIP 10 OHM 100PPM +-1% 0603 WALS L")
      (fields (field (name "POWER") "1/10W") (field (name "MFG") "WALSIN (華新)"))
      (libsource (lib "Q-Resistors") (part "RES0603 1/10W 1% 10 OHM"))
    )
    (comp (ref "R60")
      (value "10R")
      (footprint "0603-RW")
      (description "CHIP 10 OHM 100PPM +-1% 0603 WALS L")
      (fields (field (name "POWER") "1/10W") (field (name "MFG") "WALSIN (華新)"))
      (libsource (lib "Q-Resistors") (part "RES0603 1/10W 1% 10 OHM"))
    )
    (comp (ref "R61")
      (value "49.9K")
      (footprint "0603-RW")
      (description "GP CHIP RES. 49.9K OHM 1/10W 1% 0603")
      (fields (field (name "POWER") "1/10W") (field (name "Comment") "QCF011030-4992"))
      (libsource (lib "Q-Resistors") (part "RES0603 1/10W 1% 49.9K OHM"))
    )
    (comp (ref "R62")
      (value "10R")
      (footprint "0603-RW")
      (description "CHIP 10 OHM 100PPM +-1% 0603 WALS L")
      (fields (field (name "POWER") "1/10W") (field (name "MFG") "WALSIN (華新)"))
      (libsource (lib "Q-Resistors") (part "RES0603 1/10W 1% 10 OHM"))
    )
    (comp (ref "R63")
      (value "2K")
      (footprint "0603-RW")
      (description "GP CHIP RES. 2K OHM 1/10W 1% 0603")
      (fields
        (field (name "POWER") "1/10W")
        (field (name "PACKAGE") "0603")
        (field (name "Comment") "QCF011030-2001")
      )
      (libsource (lib "Q-Resistors") (part "RES0603 1/10W 1% 2K OHM"))
    )
    (comp (ref "R64")
      (value "4.99K")
      (footprint "0603-RW")
      (description "GP CHIP RES. 4.99K OHM 1/10W 1% 0603")
      (fields (field (name "POWER") "1/10W") (field (name "Comment") "QCF011030-4991"))
      (libsource (lib "Q-Resistors") (part "RES0603 1/10W 1% 4.99K OHM"))
    )
    (comp (ref "R65")
      (value "10R")
      (footprint "0603-RW")
      (description "CHIP 10 OHM 100PPM +-1% 0603 WALS L")
      (fields (field (name "POWER") "1/10W") (field (name "MFG") "WALSIN (華新)"))
      (libsource (lib "Q-Resistors") (part "RES0603 1/10W 1% 10 OHM"))
    )
    (comp (ref "R66")
      (value "2K")
      (footprint "0603-RW")
      (description "GP CHIP RES. 2K OHM 1/10W 1% 0603")
      (fields
        (field (name "POWER") "1/10W")
        (field (name "PACKAGE") "0603")
        (field (name "Comment") "QCF011030-2001")
      )
      (libsource (lib "Q-Resistors") (part "RES0603 1/10W 1% 2K OHM"))
    )
    (comp (ref "R67")
      (value "2K")
      (footprint "0603-RW")
      (description "GP CHIP RES. 2K OHM 1/10W 1% 0603")
      (fields
        (field (name "POWER") "1/10W")
        (field (name "PACKAGE") "0603")
        (field (name "Comment") "QCF011030-2001")
      )
      (libsource (lib "Q-Resistors") (part "RES0603 1/10W 1% 2K OHM"))
    )
    (comp (ref "R68")
      (value "1M")
      (footprint "0603-RW")
      (description "GP CHIP RES. 1M OHM 1/10W 1% 0603")
      (fields (field (name "Comment") "QCF011030-1004"))
      (libsource (lib "Q-Resistors") (part "RES0603 1/10W 1% 1M OHM"))
    )
    (comp (ref "R69")
      (value "1K")
      (footprint "0603-RW")
      (description "GP CHIP RES. 1K OHM 1/10W 1% 0603")
      (fields (field (name "POWER") "1/10W") (field (name "Comment") "QCF011030-1001"))
      (libsource (lib "Q-Resistors") (part "RES0603 1/10W 1% 1K OHM"))
    )
    (comp (ref "U1")
      (value "RCI000740-1001")
      (footprint "SO14")
      (description "GP IC 14P TL074CDT PLASTIC MICRO PACKAG")
      (fields (field (name "MFG") "ST") (field (name "MFG PART") "TL074C"))
      (libsource (lib "R-Semiconductors") (part "TL074C"))
    )
    (comp (ref "U2")
      (value "RCI002068-0001")
      (footprint "DMP8")
      (description "IC OP AMP NJM2068 DUAL SO-8")
      (fields
        (field (name "MFG") "JRC")
        (field (name "MFG PART") "NJM2068")
        (field (name "CREATE_NAME") "GordonL@Deftronics")
      )
      (libsource (lib "R-Semiconductors") (part "NJM2068"))
    )
    (comp (ref "U3")
      (value "RCI004580-0001")
      (footprint "DMP8")
      (description "IC OP AMP NJM4580  DUAL SO-8")
      (fields
        (field (name "MFG") "JRC")
        (field (name "MFG PART") "NJM4580")
        (field (name "CREATE_NAME") "GordonL@Deftronics")
      )
      (libsource (lib "R-Semiconductors") (part "NJM4580"))
    )
  )
  (nets
    (net (code "1") (name "+5V") (class "Default")
      (node (ref "D9") (pin "1") (pinfunction "A_1") (pintype "passive"))
      (node (ref "Q11") (pin "6") (pinfunction "D_6") (pintype "passive"))
      (node (ref "Q12") (pin "6") (pinfunction "D_6") (pintype "passive"))
    )
    (net (code "2") (name "+15V") (class "Default")
      (node (ref "C1") (pin "1") (pinfunction "1_1") (pintype "passive"))
      (node (ref "C27") (pin "1") (pinfunction "1_1") (pintype "passive"))
      (node (ref "C28") (pin "1") (pinfunction "1_1") (pintype "passive"))
      (node (ref "C29") (pin "1") (pinfunction "1_1") (pintype "passive"))
      (node (ref "C30") (pin "1") (pinfunction "1_1") (pintype "passive"))
      (node (ref "C31") (pin "1") (pinfunction "1_1") (pintype "passive"))
      (node (ref "C32") (pin "1") (pinfunction "1_1") (pintype "passive"))
      (node (ref "C33") (pin "1") (pinfunction "1_1") (pintype "passive"))
      (node (ref "C34") (pin "1") (pinfunction "1_1") (pintype "passive"))
      (node (ref "D1") (pin "2") (pinfunction "K_2") (pintype "passive"))
      (node (ref "D4") (pin "2") (pinfunction "K_2") (pintype "passive"))
      (node (ref "D5") (pin "2") (pinfunction "K_2") (pintype "passive"))
      (node (ref "D8") (pin "2") (pinfunction "K_2") (pintype "passive"))
      (node (ref "R3") (pin "2") (pinfunction "2_2") (pintype "passive"))
      (node (ref "R4") (pin "2") (pinfunction "2_2") (pintype "passive"))
      (node (ref "R5") (pin "2") (pinfunction "2_2") (pintype "passive"))
      (node (ref "U1") (pin "4") (pinfunction "+V_4") (pintype "power_in"))
      (node (ref "U2") (pin "8") (pinfunction "8_8") (pintype "passive"))
      (node (ref "U3") (pin "8") (pinfunction "8_8") (pintype "passive"))
    )
    (net (code "3") (name "-15V") (class "Default")
      (node (ref "C25") (pin "2") (pinfunction "2_2") (pintype "passive"))
      (node (ref "C40") (pin "1") (pinfunction "1_1") (pintype "passive"))
      (node (ref "C41") (pin "1") (pinfunction "1_1") (pintype "passive"))
      (node (ref "C42") (pin "1") (pinfunction "1_1") (pintype "passive"))
      (node (ref "C43") (pin "2") (pinfunction "2_2") (pintype "passive"))
      (node (ref "C44") (pin "2") (pinfunction "2_2") (pintype "passive"))
      (node (ref "C45") (pin "2") (pinfunction "2_2") (pintype "passive"))
      (node (ref "C46") (pin "2") (pinfunction "2_2") (pintype "passive"))
      (node (ref "C47") (pin "2") (pinfunction "2_2") (pintype "passive"))
      (node (ref "D1") (pin "1") (pinfunction "A_1") (pintype "passive"))
      (node (ref "D4") (pin "1") (pinfunction "A_1") (pintype "passive"))
      (node (ref "D5") (pin "1") (pinfunction "A_1") (pintype "passive"))
      (node (ref "D8") (pin "1") (pinfunction "A_1") (pintype "passive"))
      (node (ref "R46") (pin "1") (pinfunction "1_1") (pintype "passive"))
      (node (ref "R47") (pin "1") (pinfunction "1_1") (pintype "passive"))
      (node (ref "R48") (pin "1") (pinfunction "1_1") (pintype "passive"))
      (node (ref "U1") (pin "11") (pinfunction "-V_11") (pintype "power_in"))
      (node (ref "U2") (pin "4") (pinfunction "4_4") (pintype "passive"))
      (node (ref "U3") (pin "4") (pinfunction "4_4") (pintype "passive"))
    )
    (net (code "4") (name "/ADC_DR_N") (class "Default")
      (node (ref "C39") (pin "2") (pinfunction "2_2") (pintype "passive"))
      (node (ref "R58") (pin "1") (pinfunction "1_1") (pintype "passive"))
      (node (ref "R64") (pin "2") (pinfunction "2_2") (pintype "passive"))
      (node (ref "U3") (pin "7") (pinfunction "OUT_7") (pintype "passive"))
    )
    (net (code "5") (name "/ADC_DR_P") (class "Default")
      (node (ref "C26") (pin "2") (pinfunction "2_2") (pintype "passive"))
      (node (ref "R49") (pin "1") (pinfunction "1_1") (pintype "passive"))
      (node (ref "R50") (pin "2") (pinfunction "2_2") (pintype "passive"))
      (node (ref "R57") (pin "2") (pinfunction "2_2") (pintype "passive"))
      (node (ref "U3") (pin "1") (pinfunction "OUT_1") (pintype "passive"))
    )
    (net (code "6") (name "/ADC_IN_N") (class "Default")
      (node (ref "C35") (pin "2") (pinfunction "2_2") (pintype "passive"))
      (node (ref "Q12") (pin "1") (pinfunction "S_1") (pintype "passive"))
      (node (ref "Q12") (pin "4") (pinfunction "S_4") (pintype "passive"))
      (node (ref "R56") (pin "1") (pinfunction "1_1") (pintype "passive"))
      (node (ref "R64") (pin "1") (pinfunction "1_1") (pintype "passive"))
    )
    (net (code "7") (name "/ADC_IN_P") (class "Default")
      (node (ref "C35") (pin "1") (pinfunction "1_1") (pintype "passive"))
      (node (ref "Q11") (pin "1") (pinfunction "S_1") (pintype "passive"))
      (node (ref "Q11") (pin "4") (pinfunction "S_4") (pintype "passive"))
      (node (ref "R50") (pin "1") (pinfunction "1_1") (pintype "passive"))
      (node (ref "R56") (pin "2") (pinfunction "2_2") (pintype "passive"))
    )
    (net (code "8") (name "/CODEC_1_BIAS") (class "Default")
      (node (ref "C49") (pin "1") (pinfunction "1_1") (pintype "passive"))
      (node (ref "R68") (pin "2") (pinfunction "2_2") (pintype "passive"))
    )
    (net (code "9") (name "/FROM_VOL_VRA") (class "Default")
      (node (ref "R59") (pin "2") (pinfunction "2_2") (pintype "passive"))
      (node (ref "R61") (pin "2") (pinfunction "2_2") (pintype "passive"))
    )
    (net (code "10") (name "/FROM_VOL_VRB") (class "Default")
      (node (ref "C7") (pin "1") (pinfunction "1_1") (pintype "passive"))
      (node (ref "R15") (pin "2") (pinfunction "2_2") (pintype "passive"))
    )
    (net (code "11") (name "/LINE_DET") (class "Default")
      (node (ref "C8") (pin "2") (pinfunction "2_2") (pintype "passive"))
      (node (ref "R12") (pin "1") (pinfunction "1_1") (pintype "passive"))
      (node (ref "R21") (pin "2") (pinfunction "2_2") (pintype "passive"))
    )
    (net (code "12") (name "/LINE_N") (class "Default")
      (node (ref "D3") (pin "1") (pinfunction "1_1") (pintype "passive"))
      (node (ref "R22") (pin "1") (pinfunction "1_1") (pintype "passive"))
    )
    (net (code "13") (name "/LINE_P") (class "Default")
      (node (ref "D2") (pin "2") (pinfunction "2_2") (pintype "passive"))
      (node (ref "R7") (pin "1") (pinfunction "1_1") (pintype "passive"))
    )
    (net (code "14") (name "/MIC_N") (class "Default")
      (node (ref "D7") (pin "1") (pinfunction "1_1") (pintype "passive"))
      (node (ref "R39") (pin "1") (pinfunction "1_1") (pintype "passive"))
      (node (ref "R43") (pin "2") (pinfunction "2_2") (pintype "passive"))
    )
    (net (code "15") (name "/MIC_P") (class "Default")
      (node (ref "D6") (pin "2") (pinfunction "2_2") (pintype "passive"))
      (node (ref "R27") (pin "2") (pinfunction "2_2") (pintype "passive"))
      (node (ref "R32") (pin "2") (pinfunction "2_2") (pintype "passive"))
    )
    (net (code "16") (name "/TO_VOL_VRA") (class "Default")
      (node (ref "C21") (pin "2") (pinfunction "2_2") (pintype "passive"))
    )
    (net (code "17") (name "/TO_VOL_VRB") (class "Default")
      (node (ref "R14") (pin "1") (pinfunction "1_1") (pintype "passive"))
      (node (ref "R15") (pin "1") (pinfunction "1_1") (pintype "passive"))
    )
    (net (code "18") (name "GND") (class "Default")
      (node (ref "C11") (pin "2") (pinfunction "2_2") (pintype "passive"))
      (node (ref "C15") (pin "2") (pinfunction "2_2") (pintype "passive"))
      (node (ref "C16") (pin "2") (pinfunction "2_2") (pintype "passive"))
      (node (ref "C19") (pin "1") (pinfunction "1_1") (pintype "passive"))
      (node (ref "C20") (pin "2") (pinfunction "2_2") (pintype "passive"))
      (node (ref "C24") (pin "1") (pinfunction "1_1") (pintype "passive"))
      (node (ref "C27") (pin "2") (pinfunction "2_2") (pintype "passive"))
      (node (ref "C28") (pin "2") (pinfunction "2_2") (pintype "passive"))
      (node (ref "C29") (pin "2") (pinfunction "2_2") (pintype "passive"))
      (node (ref "C30") (pin "2") (pinfunction "2_2") (pintype "passive"))
      (node (ref "C31") (pin "2") (pinfunction "2_2") (pintype "passive"))
      (node (ref "C32") (pin "2") (pinfunction "2_2") (pintype "passive"))
      (node (ref "C33") (pin "2") (pinfunction "2_2") (pintype "passive"))
      (node (ref "C34") (pin "2") (pinfunction "2_2") (pintype "passive"))
      (node (ref "C40") (pin "2") (pinfunction "2_2") (pintype "passive"))
      (node (ref "C41") (pin "2") (pinfunction "2_2") (pintype "passive"))
      (node (ref "C42") (pin "2") (pinfunction "2_2") (pintype "passive"))
      (node (ref "C43") (pin "1") (pinfunction "1_1") (pintype "passive"))
      (node (ref "C44") (pin "1") (pinfunction "1_1") (pintype "passive"))
      (node (ref "C45") (pin "1") (pinfunction "1_1") (pintype "passive"))
      (node (ref "C46") (pin "1") (pinfunction "1_1") (pintype "passive"))
      (node (ref "C47") (pin "1") (pinfunction "1_1") (pintype "passive"))
      (node (ref "C49") (pin "2") (pinfunction "2_2") (pintype "passive"))
      (node (ref "C5") (pin "2") (pinfunction "2_2") (pintype "passive"))
      (node (ref "C8") (pin "1") (pinfunction "1_1") (pintype "passive"))
      (node (ref "C9") (pin "1") (pinfunction "1_1") (pintype "passive"))
      (node (ref "D10") (pin "2") (pinfunction "K_2") (pintype "passive"))
      (node (ref "D2") (pin "1") (pinfunction "1_1") (pintype "passive"))
      (node (ref "D3") (pin "2") (pinfunction "2_2") (pintype "passive"))
      (node (ref "D6") (pin "1") (pinfunction "1_1") (pintype "passive"))
      (node (ref "D7") (pin "2") (pinfunction "2_2") (pintype "passive"))
      (node (ref "Q11") (pin "3") (pinfunction "D_3") (pintype "passive"))
      (node (ref "Q12") (pin "3") (pinfunction "D_3") (pintype "passive"))
      (node (ref "R10") (pin "1") (pinfunction "1_1") (pintype "passive"))
      (node (ref "R11") (pin "1") (pinfunction "1_1") (pintype "passive"))
      (node (ref "R17") (pin "2") (pinfunction "2_2") (pintype "passive"))
      (node (ref "R18") (pin "2") (pinfunction "2_2") (pintype "passive"))
      (node (ref "R24") (pin "1") (pinfunction "1_1") (pintype "passive"))
      (node (ref "R32") (pin "1") (pinfunction "1_1") (pintype "passive"))
      (node (ref "R33") (pin "1") (pinfunction "1_1") (pintype "passive"))
      (node (ref "R39") (pin "2") (pinfunction "2_2") (pintype "passive"))
      (node (ref "R40") (pin "2") (pinfunction "2_2") (pintype "passive"))
      (node (ref "R41") (pin "2") (pinfunction "2_2") (pintype "passive"))
      (node (ref "R45") (pin "1") (pinfunction "1_1") (pintype "passive"))
      (node (ref "R51") (pin "2") (pinfunction "2_2") (pintype "passive"))
      (node (ref "R61") (pin "1") (pinfunction "1_1") (pintype "passive"))
    )
    (net (code "19") (name "Net-(C3-Pad1)") (class "Default")
      (node (ref "C3") (pin "1") (pinfunction "1_1") (pintype "passive"))
      (node (ref "R2") (pin "2") (pinfunction "2_2") (pintype "passive"))
      (node (ref "R6") (pin "1") (pinfunction "1_1") (pintype "passive"))
      (node (ref "R9") (pin "2") (pinfunction "2_2") (pintype "passive"))
    )
    (net (code "20") (name "Net-(C4-Pad1)") (class "Default")
      (node (ref "C4") (pin "1") (pinfunction "1_1") (pintype "passive"))
      (node (ref "C5") (pin "1") (pinfunction "1_1") (pintype "passive"))
      (node (ref "D1") (pin "3") (pinfunction "3_3") (pintype "passive"))
      (node (ref "R10") (pin "2") (pinfunction "2_2") (pintype "passive"))
      (node (ref "R7") (pin "2") (pinfunction "2_2") (pintype "passive"))
    )
    (net (code "21") (name "Net-(C4-Pad2)") (class "Default")
      (node (ref "C4") (pin "2") (pinfunction "2_2") (pintype "passive"))
      (node (ref "R11") (pin "2") (pinfunction "2_2") (pintype "passive"))
      (node (ref "R8") (pin "1") (pinfunction "1_1") (pintype "passive"))
    )
    (net (code "22") (name "Net-(C7-Pad2)") (class "Default")
      (node (ref "C7") (pin "2") (pinfunction "2_2") (pintype "passive"))
      (node (ref "R16") (pin "2") (pinfunction "2_2") (pintype "passive"))
    )
    (net (code "23") (name "Net-(C11-Pad1)") (class "Default")
      (node (ref "C11") (pin "1") (pinfunction "1_1") (pintype "passive"))
      (node (ref "R19") (pin "1") (pinfunction "1_1") (pintype "passive"))
      (node (ref "R20") (pin "1") (pinfunction "1_1") (pintype "passive"))
      (node (ref "R24") (pin "2") (pinfunction "2_2") (pintype "passive"))
    )
    (net (code "24") (name "Net-(C12-Pad1)") (class "Default")
      (node (ref "C12") (pin "1") (pinfunction "1_1") (pintype "passive"))
      (node (ref "C9") (pin "2") (pinfunction "2_2") (pintype "passive"))
      (node (ref "D4") (pin "3") (pinfunction "3_3") (pintype "passive"))
      (node (ref "R17") (pin "1") (pinfunction "1_1") (pintype "passive"))
      (node (ref "R22") (pin "2") (pinfunction "2_2") (pintype "passive"))
    )
    (net (code "25") (name "Net-(C12-Pad2)") (class "Default")
      (node (ref "C12") (pin "2") (pinfunction "2_2") (pintype "passive"))
      (node (ref "R18") (pin "1") (pinfunction "1_1") (pintype "passive"))
      (node (ref "R23") (pin "1") (pinfunction "1_1") (pintype "passive"))
    )
    (net (code "26") (name "Net-(C14-Pad1)") (class "Default")
      (node (ref "C14") (pin "1") (pinfunction "1_1") (pintype "passive"))
      (node (ref "C15") (pin "1") (pinfunction "1_1") (pintype "passive"))
      (node (ref "R27") (pin "1") (pinfunction "1_1") (pintype "passive"))
    )
    (net (code "27") (name "Net-(C14-Pad2)") (class "Default")
      (node (ref "C14") (pin "2") (pinfunction "2_2") (pintype "passive"))
      (node (ref "C16") (pin "1") (pinfunction "1_1") (pintype "passive"))
      (node (ref "C17") (pin "1") (pinfunction "1_1") (pintype "passive"))
      (node (ref "D5") (pin "3") (pinfunction "3_3") (pintype "passive"))
      (node (ref "R21") (pin "1") (pinfunction "1_1") (pintype "passive"))
      (node (ref "R25") (pin "2") (pinfunction "2_2") (pintype "passive"))
      (node (ref "R28") (pin "2") (pinfunction "2_2") (pintype "passive"))
      (node (ref "R30") (pin "2") (pinfunction "2_2") (pintype "passive"))
      (node (ref "R33") (pin "2") (pinfunction "2_2") (pintype "passive"))
      (node (ref "R34") (pin "2") (pinfunction "2_2") (pintype "passive"))
    )
    (net (code "28") (name "Net-(C17-Pad2)") (class "Default")
      (node (ref "C17") (pin "2") (pinfunction "2_2") (pintype "passive"))
      (node (ref "C20") (pin "1") (pinfunction "1_1") (pintype "passive"))
      (node (ref "C22") (pin "2") (pinfunction "2_2") (pintype "passive"))
      (node (ref "D8") (pin "3") (pinfunction "3_3") (pintype "passive"))
      (node (ref "R26") (pin "1") (pinfunction "1_1") (pintype "passive"))
      (node (ref "R29") (pin "1") (pinfunction "1_1") (pintype "passive"))
      (node (ref "R31") (pin "1") (pinfunction "1_1") (pintype "passive"))
      (node (ref "R34") (pin "1") (pinfunction "1_1") (pintype "passive"))
      (node (ref "R40") (pin "1") (pinfunction "1_1") (pintype "passive"))
      (node (ref "R41") (pin "1") (pinfunction "1_1") (pintype "passive"))
    )
    (net (code "29") (name "Net-(C19-Pad2)") (class "Default")
      (node (ref "C19") (pin "2") (pinfunction "2_2") (pintype "passive"))
      (node (ref "C22") (pin "1") (pinfunction "1_1") (pintype "passive"))
      (node (ref "R43") (pin "1") (pinfunction "1_1") (pintype "passive"))
    )
    (net (code "30") (name "Net-(C26-Pad1)") (class "Default")
      (node (ref "C26") (pin "1") (pinfunction "1_1") (pintype "passive"))
      (node (ref "R49") (pin "2") (pinfunction "2_2") (pintype "passive"))
      (node (ref "R54") (pin "1") (pinfunction "1_1") (pintype "passive"))
      (node (ref "R55") (pin "2") (pinfunction "2_2") (pintype "passive"))
    )
    (net (code "31") (name "Net-(C36-Pad1)") (class "Default")
      (node (ref "C36") (pin "1") (pinfunction "1_1") (pintype "passive"))
      (node (ref "R54") (pin "2") (pinfunction "2_2") (pintype "passive"))
    )
    (net (code "32") (name "Net-(C39-Pad1)") (class "Default")
      (node (ref "C39") (pin "1") (pinfunction "1_1") (pintype "passive"))
      (node (ref "R57") (pin "1") (pinfunction "1_1") (pintype "passive"))
      (node (ref "R58") (pin "2") (pinfunction "2_2") (pintype "passive"))
      (node (ref "R62") (pin "2") (pinfunction "2_2") (pintype "passive"))
    )
    (net (code "33") (name "Net-(D9-K)") (class "Default")
      (node (ref "D9") (pin "2") (pinfunction "K_2") (pintype "passive"))
      (node (ref "Q11") (pin "5") (pinfunction "G_5") (pintype "passive"))
      (node (ref "Q12") (pin "5") (pinfunction "G_5") (pintype "passive"))
      (node (ref "R69") (pin "2") (pinfunction "2_2") (pintype "passive"))
    )
    (net (code "34") (name "Net-(D10-A)") (class "Default")
      (node (ref "D10") (pin "1") (pinfunction "A_1") (pintype "passive"))
      (node (ref "Q11") (pin "2") (pinfunction "G_2") (pintype "passive"))
      (node (ref "Q12") (pin "2") (pinfunction "G_2") (pintype "passive"))
      (node (ref "R69") (pin "1") (pinfunction "1_1") (pintype "passive"))
    )
    (net (code "35") (name "Net-(Q1-B)") (class "Default")
      (node (ref "C1") (pin "2") (pinfunction "2_2") (pintype "passive"))
      (node (ref "Q1") (pin "1") (pinfunction "B_1") (pintype "passive"))
      (node (ref "Q2") (pin "1") (pinfunction "B_1") (pintype "passive"))
      (node (ref "R37") (pin "2") (pinfunction "2_2") (pintype "passive"))
      (node (ref "R4") (pin "1") (pinfunction "1_1") (pintype "passive"))
    )
    (net (code "36") (name "Net-(Q1-C)") (class "Default")
      (node (ref "C13") (pin "2") (pinfunction "2_2") (pintype "passive"))
      (node (ref "Q1") (pin "3") (pinfunction "C_3") (pintype "passive"))
      (node (ref "Q3") (pin "2") (pinfunction "E_2") (pintype "passive"))
      (node (ref "Q4") (pin "2") (pinfunction "E_2") (pintype "passive"))
      (node (ref "Q5") (pin "2") (pinfunction "E_2") (pintype "passive"))
      (node (ref "R14") (pin "2") (pinfunction "2_2") (pintype "passive"))
    )
    (net (code "37") (name "Net-(Q1-E)") (class "Default")
      (node (ref "Q1") (pin "2") (pinfunction "E_2") (pintype "passive"))
      (node (ref "R3") (pin "1") (pinfunction "1_1") (pintype "passive"))
    )
    (net (code "38") (name "Net-(Q2-C)") (class "Default")
      (node (ref "C13") (pin "1") (pinfunction "1_1") (pintype "passive"))
      (node (ref "Q2") (pin "3") (pinfunction "C_3") (pintype "passive"))
      (node (ref "Q6") (pin "2") (pinfunction "E_2") (pintype "passive"))
      (node (ref "Q7") (pin "2") (pinfunction "E_2") (pintype "passive"))
      (node (ref "Q8") (pin "2") (pinfunction "E_2") (pintype "passive"))
      (node (ref "R16") (pin "1") (pinfunction "1_1") (pintype "passive"))
    )
    (net (code "39") (name "Net-(Q2-E)") (class "Default")
      (node (ref "Q2") (pin "2") (pinfunction "E_2") (pintype "passive"))
      (node (ref "R5") (pin "1") (pinfunction "1_1") (pintype "passive"))
    )
    (net (code "40") (name "Net-(Q3-B)") (class "Default")
      (node (ref "Q3") (pin "1") (pinfunction "B_1") (pintype "passive"))
      (node (ref "R25") (pin "1") (pinfunction "1_1") (pintype "passive"))
    )
    (net (code "41") (name "Net-(Q3-C)") (class "Default")
      (node (ref "Q3") (pin "3") (pinfunction "C_3") (pintype "passive"))
      (node (ref "Q4") (pin "3") (pinfunction "C_3") (pintype "passive"))
      (node (ref "Q5") (pin "3") (pinfunction "C_3") (pintype "passive"))
      (node (ref "R36") (pin "2") (pinfunction "2_2") (pintype "passive"))
    )
    (net (code "42") (name "Net-(Q4-B)") (class "Default")
      (node (ref "Q4") (pin "1") (pinfunction "B_1") (pintype "passive"))
      (node (ref "R28") (pin "1") (pinfunction "1_1") (pintype "passive"))
    )
    (net (code "43") (name "Net-(Q5-B)") (class "Default")
      (node (ref "Q5") (pin "1") (pinfunction "B_1") (pintype "passive"))
      (node (ref "R30") (pin "1") (pinfunction "1_1") (pintype "passive"))
    )
    (net (code "44") (name "Net-(Q6-B)") (class "Default")
      (node (ref "Q6") (pin "1") (pinfunction "B_1") (pintype "passive"))
      (node (ref "R31") (pin "2") (pinfunction "2_2") (pintype "passive"))
    )
    (net (code "45") (name "Net-(Q6-C)") (class "Default")
      (node (ref "Q6") (pin "3") (pinfunction "C_3") (pintype "passive"))
      (node (ref "Q7") (pin "3") (pinfunction "C_3") (pintype "passive"))
      (node (ref "Q8") (pin "3") (pinfunction "C_3") (pintype "passive"))
      (node (ref "R38") (pin "2") (pinfunction "2_2") (pintype "passive"))
    )
    (net (code "46") (name "Net-(Q7-B)") (class "Default")
      (node (ref "Q7") (pin "1") (pinfunction "B_1") (pintype "passive"))
      (node (ref "R29") (pin "2") (pinfunction "2_2") (pintype "passive"))
    )
    (net (code "47") (name "Net-(Q8-B)") (class "Default")
      (node (ref "Q8") (pin "1") (pinfunction "B_1") (pintype "passive"))
      (node (ref "R26") (pin "2") (pinfunction "2_2") (pintype "passive"))
    )
    (net (code "48") (name "Net-(Q9-C)") (class "Default")
      (node (ref "C18") (pin "2") (pinfunction "2_2") (pintype "passive"))
      (node (ref "Q9") (pin "3") (pinfunction "C_3") (pintype "passive"))
      (node (ref "R35") (pin "2") (pinfunction "2_2") (pintype "passive"))
      (node (ref "R36") (pin "1") (pinfunction "1_1") (pintype "passive"))
      (node (ref "R42") (pin "2") (pinfunction "2_2") (pintype "passive"))
    )
    (net (code "49") (name "Net-(Q9-E)") (class "Default")
      (node (ref "Q9") (pin "2") (pinfunction "E_2") (pintype "passive"))
      (node (ref "R46") (pin "2") (pinfunction "2_2") (pintype "passive"))
    )
    (net (code "50") (name "Net-(Q10-B)") (class "Default")
      (node (ref "C25") (pin "1") (pinfunction "1_1") (pintype "passive"))
      (node (ref "Q10") (pin "1") (pinfunction "B_1") (pintype "passive"))
      (node (ref "Q9") (pin "1") (pinfunction "B_1") (pintype "passive"))
      (node (ref "R37") (pin "1") (pinfunction "1_1") (pintype "passive"))
      (node (ref "R47") (pin "2") (pinfunction "2_2") (pintype "passive"))
    )
    (net (code "51") (name "Net-(Q10-C)") (class "Default")
      (node (ref "C24") (pin "2") (pinfunction "2_2") (pintype "passive"))
      (node (ref "Q10") (pin "3") (pinfunction "C_3") (pintype "passive"))
      (node (ref "R38") (pin "1") (pinfunction "1_1") (pintype "passive"))
      (node (ref "R44") (pin "2") (pinfunction "2_2") (pintype "passive"))
      (node (ref "R45") (pin "2") (pinfunction "2_2") (pintype "passive"))
    )
    (net (code "52") (name "Net-(Q10-E)") (class "Default")
      (node (ref "Q10") (pin "2") (pinfunction "E_2") (pintype "passive"))
      (node (ref "R48") (pin "2") (pinfunction "2_2") (pintype "passive"))
    )
    (net (code "53") (name "Net-(R51-Pad1)") (class "Default")
      (node (ref "R51") (pin "1") (pinfunction "1_1") (pintype "passive"))
      (node (ref "R52") (pin "2") (pinfunction "2_2") (pintype "passive"))
      (node (ref "R53") (pin "2") (pinfunction "2_2") (pintype "passive"))
    )
    (net (code "54") (name "Net-(R60-Pad2)") (class "Default")
      (node (ref "R60") (pin "2") (pinfunction "2_2") (pintype "passive"))
      (node (ref "R63") (pin "2") (pinfunction "2_2") (pintype "passive"))
    )
    (net (code "55") (name "Net-(R65-Pad1)") (class "Default")
      (node (ref "R65") (pin "1") (pinfunction "1_1") (pintype "passive"))
      (node (ref "R66") (pin "2") (pinfunction "2_2") (pintype "passive"))
    )
    (net (code "56") (name "Net-(U1A-IN+)") (class "Default")
      (node (ref "C2") (pin "2") (pinfunction "2_2") (pintype "passive"))
      (node (ref "R8") (pin "2") (pinfunction "2_2") (pintype "passive"))
      (node (ref "U1") (pin "3") (pinfunction "IN+_3") (pintype "input"))
    )
    (net (code "57") (name "Net-(U1A-IN-)") (class "Default")
      (node (ref "C2") (pin "1") (pinfunction "1_1") (pintype "passive"))
      (node (ref "R1") (pin "1") (pinfunction "1_1") (pintype "passive"))
      (node (ref "U1") (pin "2") (pinfunction "IN-_2") (pintype "input"))
    )
    (net (code "58") (name "Net-(U1A-OUT)") (class "Default")
      (node (ref "R1") (pin "2") (pinfunction "2_2") (pintype "passive"))
      (node (ref "R6") (pin "2") (pinfunction "2_2") (pintype "passive"))
      (node (ref "U1") (pin "1") (pinfunction "OUT_1") (pintype "output"))
    )
    (net (code "59") (name "Net-(U1B-IN+)") (class "Default")
      (node (ref "C10") (pin "2") (pinfunction "2_2") (pintype "passive"))
      (node (ref "R23") (pin "2") (pinfunction "2_2") (pintype "passive"))
      (node (ref "U1") (pin "5") (pinfunction "IN+_5") (pintype "input"))
    )
    (net (code "60") (name "Net-(U1B-IN-)") (class "Default")
      (node (ref "C10") (pin "1") (pinfunction "1_1") (pintype "passive"))
      (node (ref "R13") (pin "1") (pinfunction "1_1") (pintype "passive"))
      (node (ref "U1") (pin "6") (pinfunction "IN-_6") (pintype "input"))
    )
    (net (code "61") (name "Net-(U1B-OUT)") (class "Default")
      (node (ref "R13") (pin "2") (pinfunction "2_2") (pintype "passive"))
      (node (ref "R20") (pin "2") (pinfunction "2_2") (pintype "passive"))
      (node (ref "U1") (pin "7") (pinfunction "OUT_7") (pintype "output"))
    )
    (net (code "62") (name "Net-(U1C-IN+)") (class "Default")
      (node (ref "C37") (pin "1") (pinfunction "1_1") (pintype "passive"))
      (node (ref "R59") (pin "1") (pinfunction "1_1") (pintype "passive"))
      (node (ref "U1") (pin "10") (pinfunction "IN+_10") (pintype "input"))
    )
    (net (code "63") (name "Net-(U1C-IN-)") (class "Default")
      (node (ref "C37") (pin "2") (pinfunction "2_2") (pintype "passive"))
      (node (ref "R53") (pin "1") (pinfunction "1_1") (pintype "passive"))
      (node (ref "U1") (pin "9") (pinfunction "IN-_9") (pintype "input"))
    )
    (net (code "64") (name "Net-(U1C-OUT)") (class "Default")
      (node (ref "C36") (pin "2") (pinfunction "2_2") (pintype "passive"))
      (node (ref "R52") (pin "1") (pinfunction "1_1") (pintype "passive"))
      (node (ref "U1") (pin "8") (pinfunction "OUT_8") (pintype "output"))
    )
    (net (code "65") (name "Net-(U1D-IN+)") (class "Default")
      (node (ref "R68") (pin "1") (pinfunction "1_1") (pintype "passive"))
      (node (ref "U1") (pin "12") (pinfunction "IN+_12") (pintype "input"))
    )
    (net (code "66") (name "Net-(U1D-IN-)") (class "Default")
      (node (ref "R67") (pin "1") (pinfunction "1_1") (pintype "passive"))
      (node (ref "U1") (pin "13") (pinfunction "IN-_13") (pintype "input"))
    )
    (net (code "67") (name "Net-(U1D-OUT)") (class "Default")
      (node (ref "R63") (pin "1") (pinfunction "1_1") (pintype "passive"))
      (node (ref "R66") (pin "1") (pinfunction "1_1") (pintype "passive"))
      (node (ref "R67") (pin "2") (pinfunction "2_2") (pintype "passive"))
      (node (ref "U1") (pin "14") (pinfunction "OUT_14") (pintype "output"))
    )
    (net (code "68") (name "Net-(U2A-IN+)") (class "Default")
      (node (ref "C6") (pin "2") (pinfunction "2_2") (pintype "passive"))
      (node (ref "R19") (pin "2") (pinfunction "2_2") (pintype "passive"))
      (node (ref "U2") (pin "3") (pinfunction "IN+_3") (pintype "passive"))
    )
    (net (code "69") (name "Net-(U2A-IN-)") (class "Default")
      (node (ref "C6") (pin "1") (pinfunction "1_1") (pintype "passive"))
      (node (ref "R9") (pin "1") (pinfunction "1_1") (pintype "passive"))
      (node (ref "U2") (pin "2") (pinfunction "IN-_2") (pintype "passive"))
    )
    (net (code "70") (name "Net-(U2A-OUT)") (class "Default")
      (node (ref "C3") (pin "2") (pinfunction "2_2") (pintype "passive"))
      (node (ref "R12") (pin "2") (pinfunction "2_2") (pintype "passive"))
      (node (ref "R2") (pin "1") (pinfunction "1_1") (pintype "passive"))
      (node (ref "U2") (pin "1") (pinfunction "OUT_1") (pintype "passive"))
    )
    (net (code "71") (name "Net-(U2B-IN+)") (class "Default")
      (node (ref "C23") (pin "2") (pinfunction "2_2") (pintype "passive"))
      (node (ref "R44") (pin "1") (pinfunction "1_1") (pintype "passive"))
      (node (ref "U2") (pin "5") (pinfunction "IN+_5") (pintype "passive"))
    )
    (net (code "72") (name "Net-(U2B-IN-)") (class "Default")
      (node (ref "C23") (pin "1") (pinfunction "1_1") (pintype "passive"))
      (node (ref "R42") (pin "1") (pinfunction "1_1") (pintype "passive"))
      (node (ref "U2") (pin "6") (pinfunction "IN-_6") (pintype "passive"))
    )
    (net (code "73") (name "Net-(U2B-OUT)") (class "Default")
      (node (ref "C18") (pin "1") (pinfunction "1_1") (pintype "passive"))
      (node (ref "C21") (pin "1") (pinfunction "1_1") (pintype "passive"))
      (node (ref "R35") (pin "1") (pinfunction "1_1") (pintype "passive"))
      (node (ref "U2") (pin "7") (pinfunction "OUT_7") (pintype "passive"))
    )
    (net (code "74") (name "Net-(U3A-IN+)") (class "Default")
      (node (ref "C38") (pin "1") (pinfunction "1_1") (pintype "passive"))
      (node (ref "R60") (pin "1") (pinfunction "1_1") (pintype "passive"))
      (node (ref "U3") (pin "3") (pinfunction "IN+_3") (pintype "passive"))
    )
    (net (code "75") (name "Net-(U3A-IN-)") (class "Default")
      (node (ref "C38") (pin "2") (pinfunction "2_2") (pintype "passive"))
      (node (ref "R55") (pin "1") (pinfunction "1_1") (pintype "passive"))
      (node (ref "U3") (pin "2") (pinfunction "IN-_2") (pintype "passive"))
    )
    (net (code "76") (name "Net-(U3B-IN+)") (class "Default")
      (node (ref "C48") (pin "1") (pinfunction "1_1") (pintype "passive"))
      (node (ref "R65") (pin "2") (pinfunction "2_2") (pintype "passive"))
      (node (ref "U3") (pin "5") (pinfunction "IN+_5") (pintype "passive"))
    )
    (net (code "77") (name "Net-(U3B-IN-)") (class "Default")
      (node (ref "C48") (pin "2") (pinfunction "2_2") (pintype "passive"))
      (node (ref "R62") (pin "1") (pinfunction "1_1") (pintype "passive"))
      (node (ref "U3") (pin "6") (pinfunction "IN-_6") (pintype "passive"))
    )
  )
)
